# micromousev2.net
KiCad netlist of a schematic drawn in EAGLE
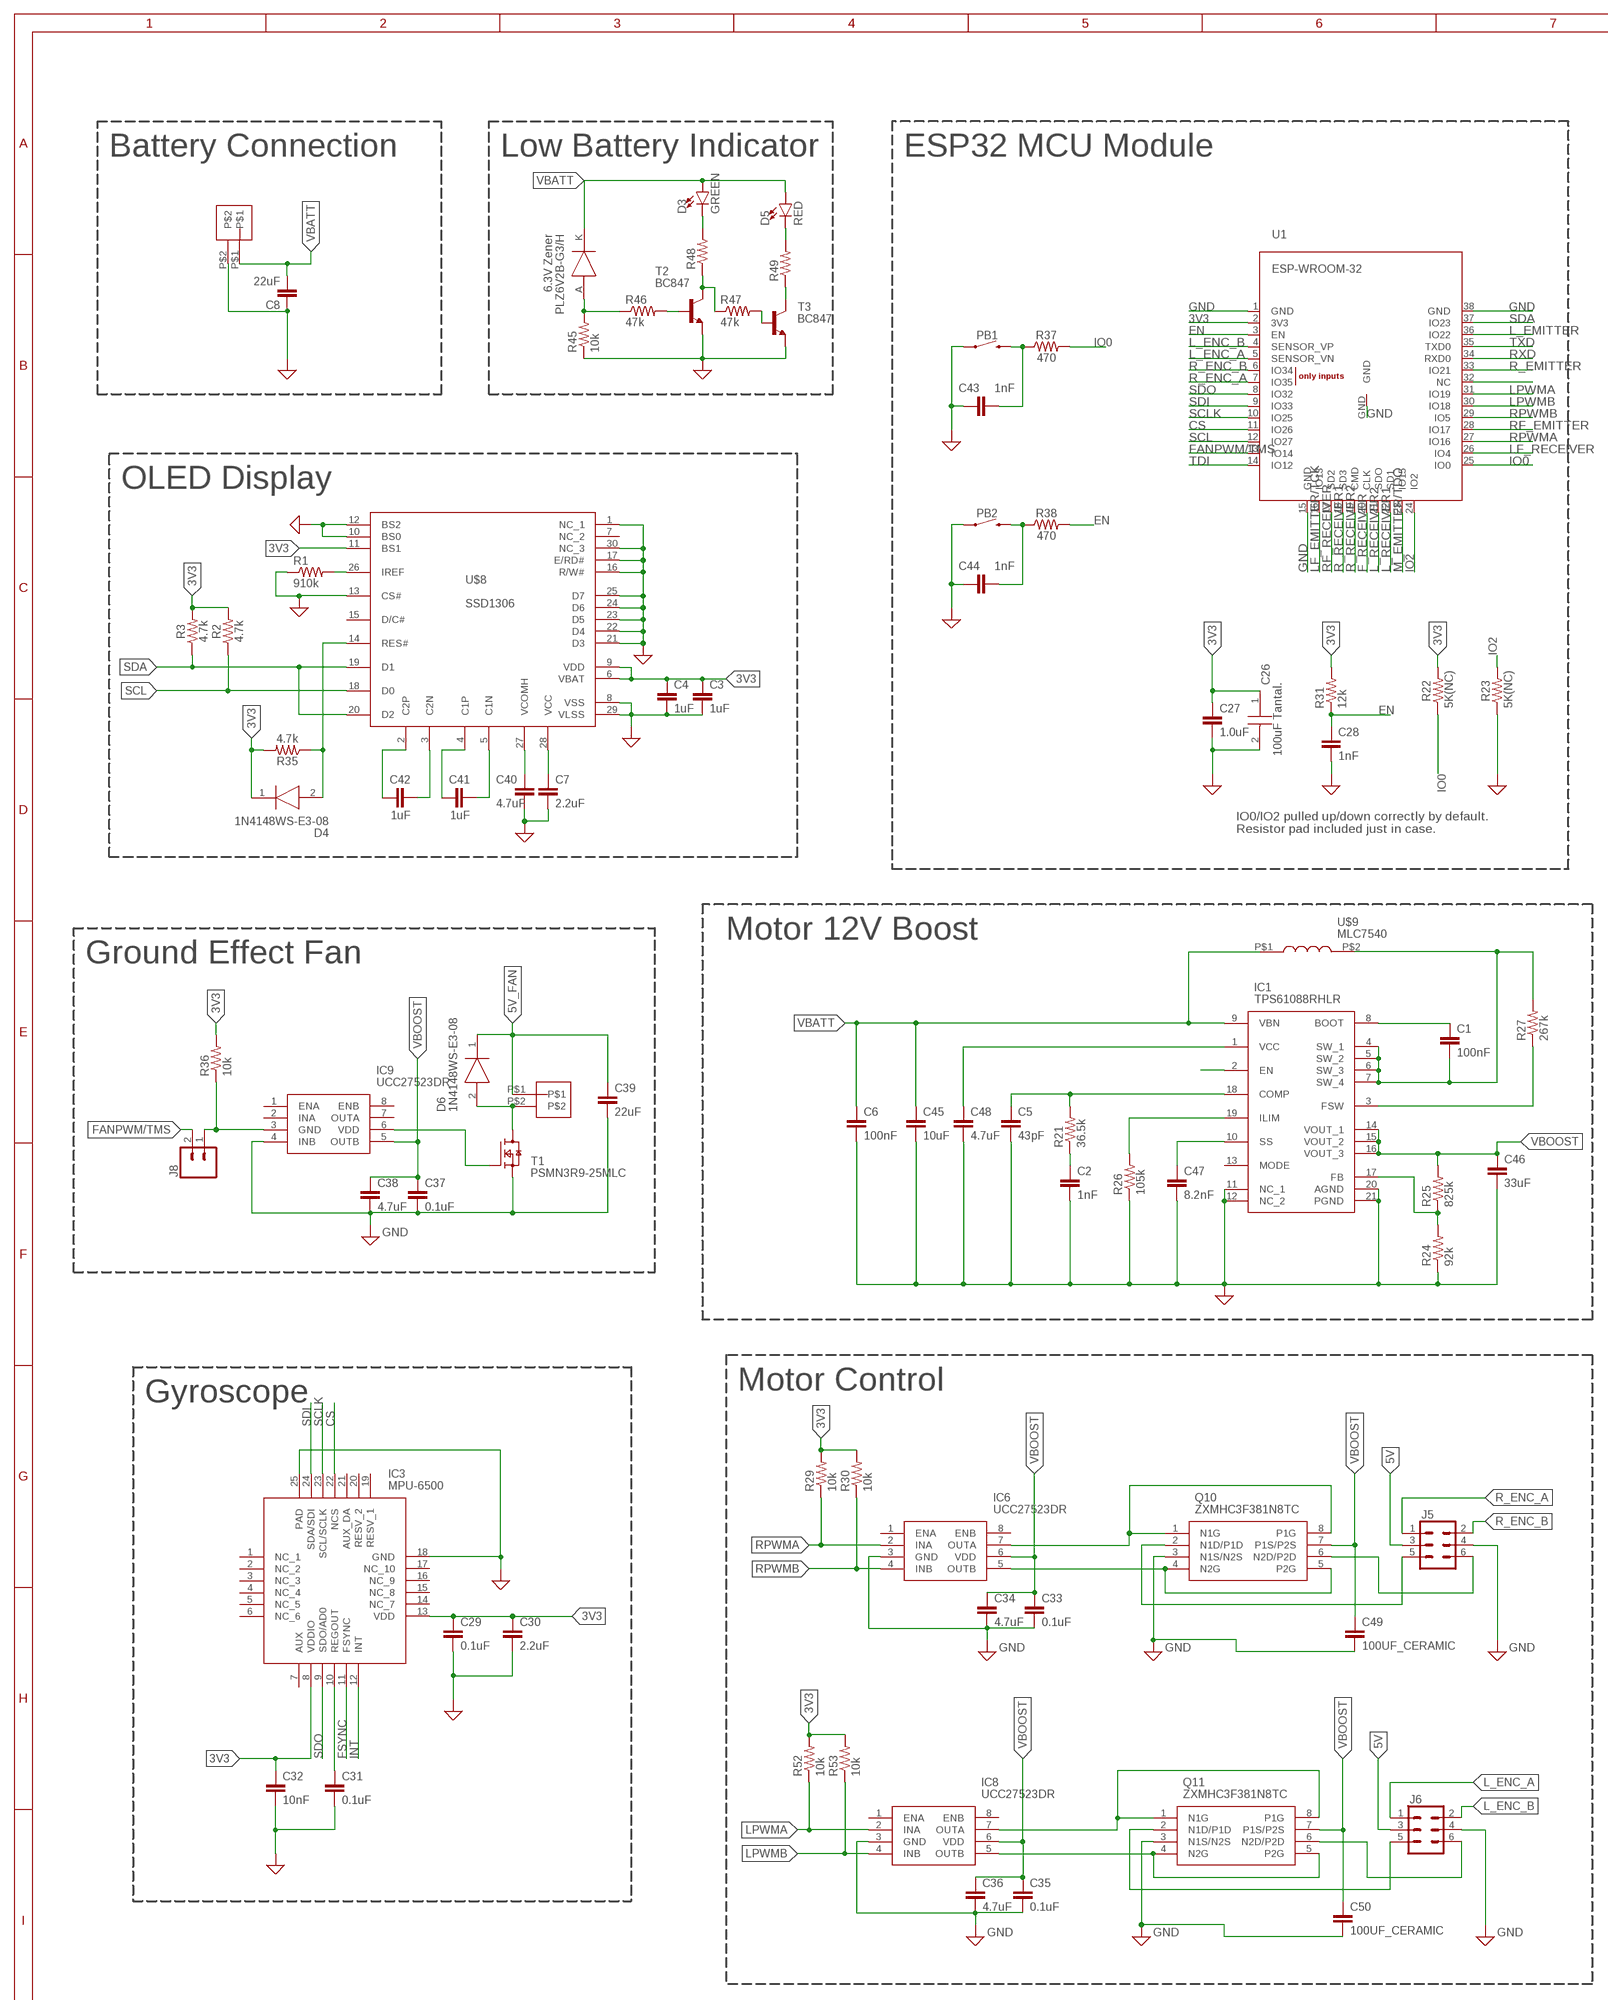
[diagram p0: schematic, sheet 1, part 1 of 2]
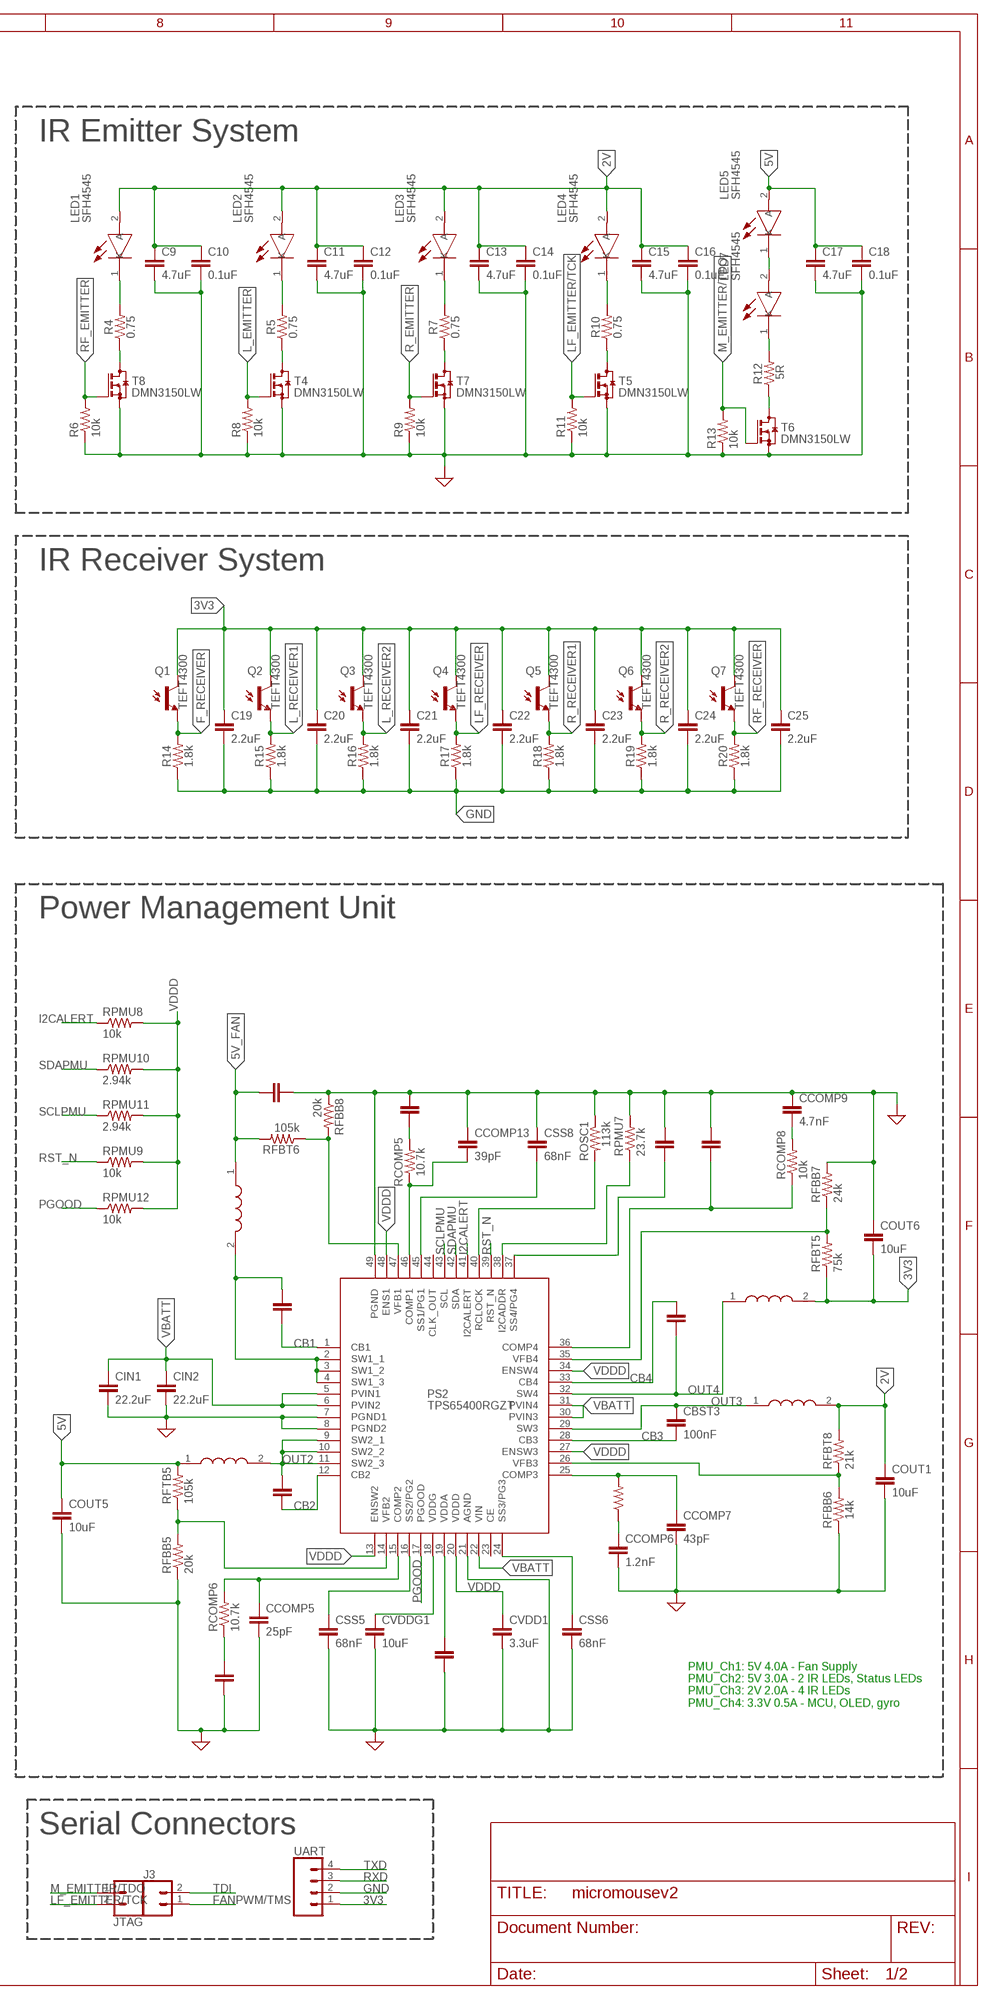
[diagram p1: schematic, sheet 1, part 2 of 2]
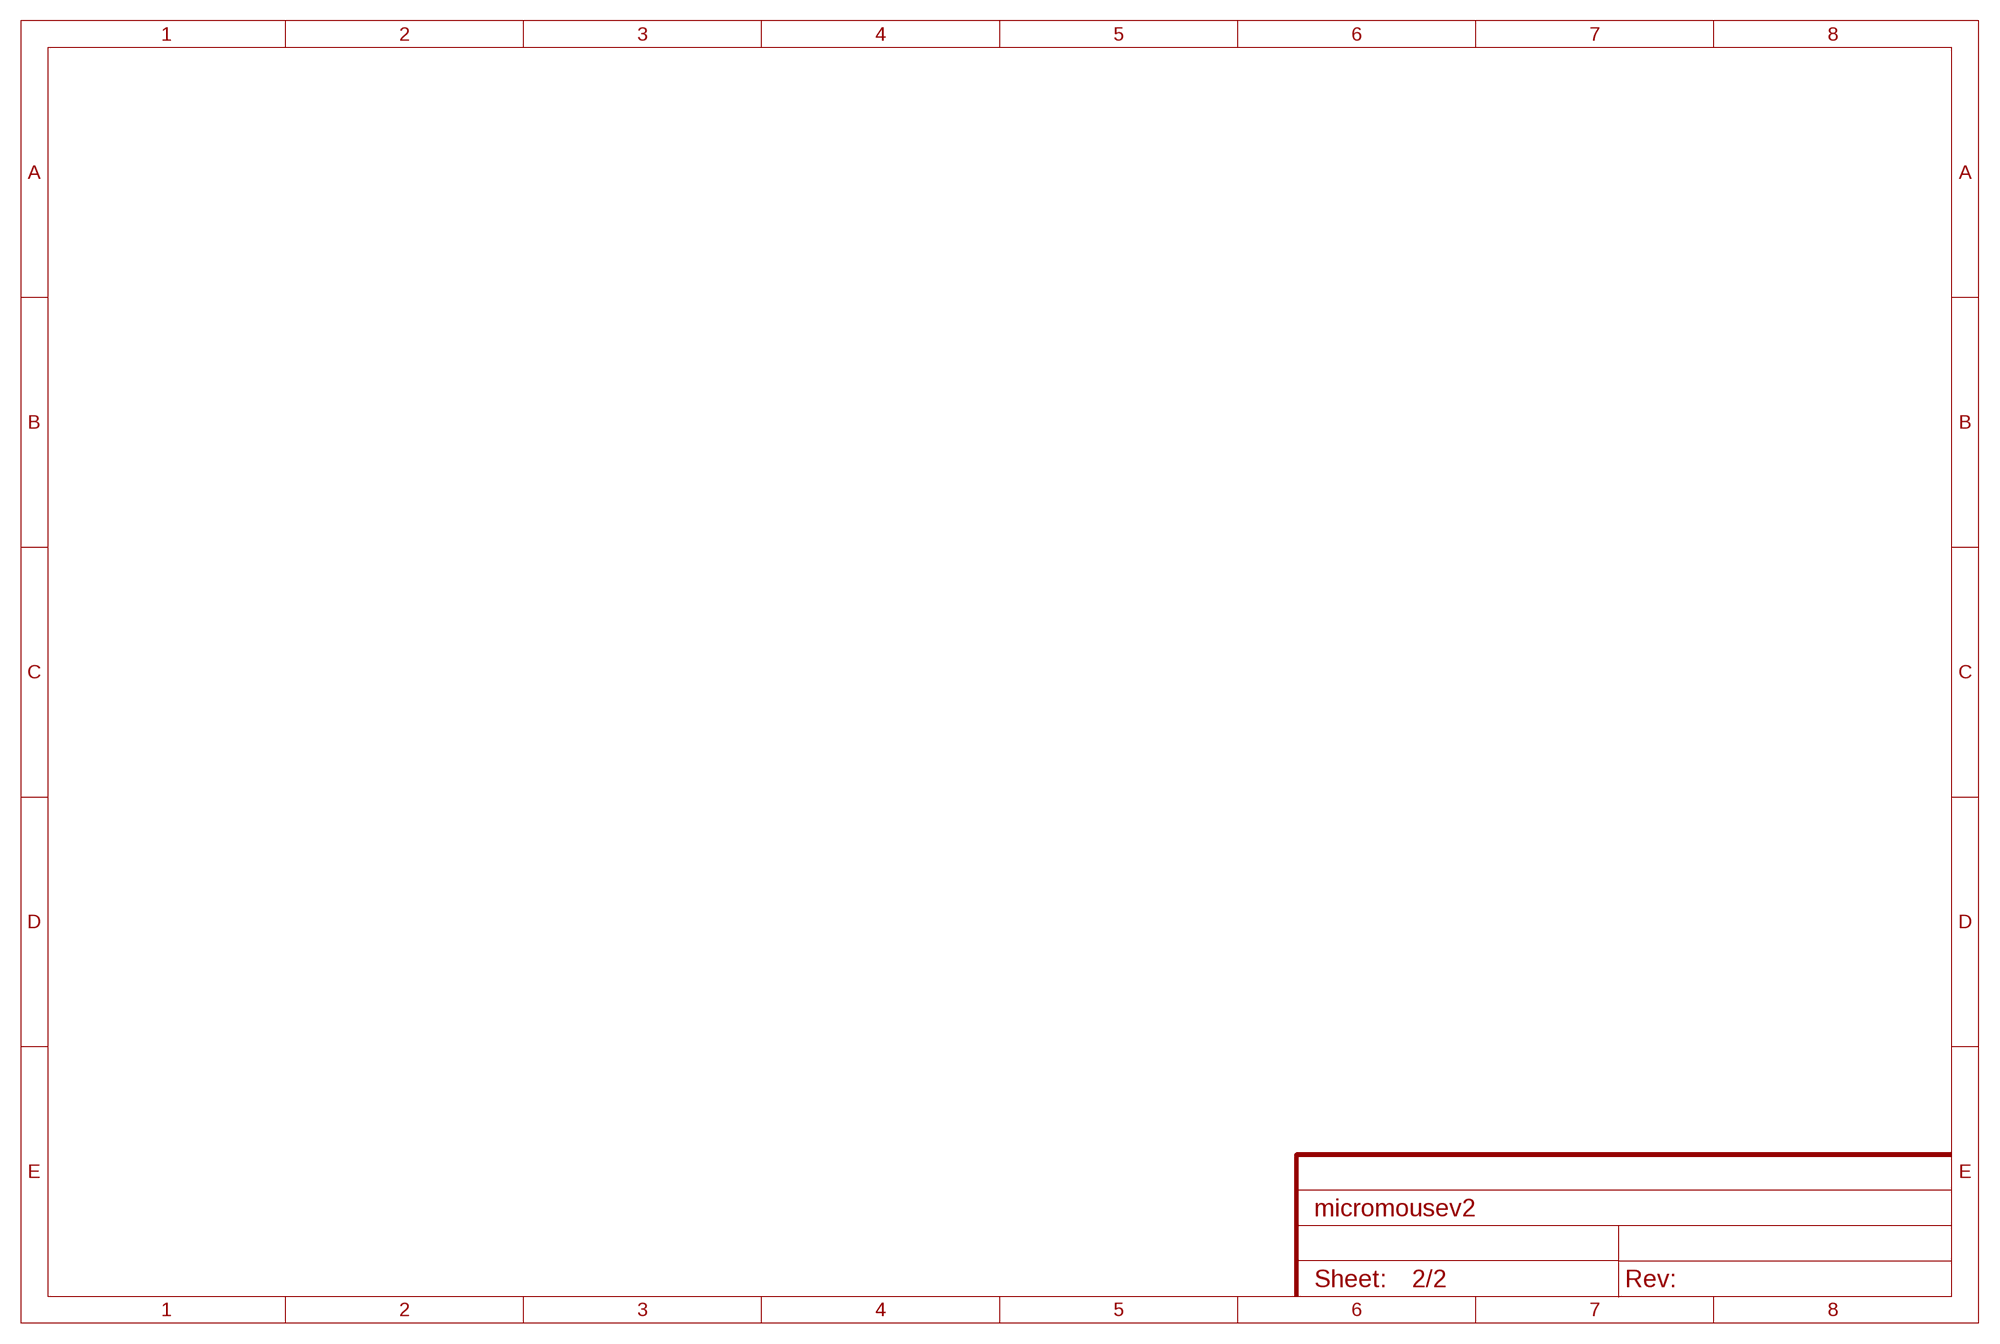
[diagram p2: schematic, sheet 2]

(export (version "E")
  (design (tool "Eeschema 10.0.6"))
  (components
    (comp (ref "C1")
      (value "100nF")
      (footprint "eagle-import:C0402")
      (libsource (lib "eagle-import") (part "C-EUC0402"))
    )
    (comp (ref "C2")
      (value "1nF")
      (footprint "eagle-import:C0805")
      (libsource (lib "eagle-import") (part "C-EUC0805"))
    )
    (comp (ref "C3")
      (value "1uF")
      (footprint "eagle-import:C0402")
      (libsource (lib "eagle-import") (part "resistor_348_C-EUC0402"))
    )
    (comp (ref "C4")
      (value "1uF")
      (footprint "eagle-import:C0402")
      (libsource (lib "eagle-import") (part "resistor_348_C-EUC0402"))
    )
    (comp (ref "C5")
      (value "43pF")
      (footprint "eagle-import:C0402")
      (libsource (lib "eagle-import") (part "C-EUC0402"))
    )
    (comp (ref "C6")
      (value "100nF")
      (footprint "eagle-import:C0805")
      (libsource (lib "eagle-import") (part "C-EUC0805"))
    )
    (comp (ref "C7")
      (value "2.2uF")
      (footprint "eagle-import:C0402")
      (libsource (lib "eagle-import") (part "resistor_348_C-EUC0402"))
    )
    (comp (ref "C8")
      (value "22uF")
      (footprint "eagle-import:0805")
      (libsource (lib "eagle-import") (part "22UF-0805-6.3V-20%"))
    )
    (comp (ref "C9")
      (value "4.7uF")
      (footprint "eagle-import:0603")
      (libsource (lib "eagle-import") (part "4.7UF0603"))
    )
    (comp (ref "C10")
      (value "0.1uF")
      (footprint "eagle-import:C0402")
      (libsource (lib "eagle-import") (part "C-EUC0402"))
    )
    (comp (ref "C11")
      (value "4.7uF")
      (footprint "eagle-import:0603")
      (libsource (lib "eagle-import") (part "4.7UF0603"))
    )
    (comp (ref "C12")
      (value "0.1uF")
      (footprint "eagle-import:C0402")
      (libsource (lib "eagle-import") (part "C-EUC0402"))
    )
    (comp (ref "C13")
      (value "4.7uF")
      (footprint "eagle-import:0603")
      (libsource (lib "eagle-import") (part "4.7UF0603"))
    )
    (comp (ref "C14")
      (value "0.1uF")
      (footprint "eagle-import:C0402")
      (libsource (lib "eagle-import") (part "C-EUC0402"))
    )
    (comp (ref "C15")
      (value "4.7uF")
      (footprint "eagle-import:0603")
      (libsource (lib "eagle-import") (part "4.7UF0603"))
    )
    (comp (ref "C16")
      (value "0.1uF")
      (footprint "eagle-import:C0402")
      (libsource (lib "eagle-import") (part "C-EUC0402"))
    )
    (comp (ref "C17")
      (value "4.7uF")
      (footprint "eagle-import:0603")
      (libsource (lib "eagle-import") (part "4.7UF0603"))
    )
    (comp (ref "C18")
      (value "0.1uF")
      (footprint "eagle-import:C0402")
      (libsource (lib "eagle-import") (part "C-EUC0402"))
    )
    (comp (ref "C19")
      (value "2.2uF")
      (footprint "eagle-import:0603")
      (libsource (lib "eagle-import") (part "2.2UF-0603-10V-20%"))
    )
    (comp (ref "C20")
      (value "2.2uF")
      (footprint "eagle-import:0603")
      (libsource (lib "eagle-import") (part "2.2UF-0603-10V-20%"))
    )
    (comp (ref "C21")
      (value "2.2uF")
      (footprint "eagle-import:0603")
      (libsource (lib "eagle-import") (part "2.2UF-0603-10V-20%"))
    )
    (comp (ref "C22")
      (value "2.2uF")
      (footprint "eagle-import:0603")
      (libsource (lib "eagle-import") (part "2.2UF-0603-10V-20%"))
    )
    (comp (ref "C23")
      (value "2.2uF")
      (footprint "eagle-import:0603")
      (libsource (lib "eagle-import") (part "2.2UF-0603-10V-20%"))
    )
    (comp (ref "C24")
      (value "2.2uF")
      (footprint "eagle-import:0603")
      (libsource (lib "eagle-import") (part "2.2UF-0603-10V-20%"))
    )
    (comp (ref "C25")
      (value "2.2uF")
      (footprint "eagle-import:0603")
      (libsource (lib "eagle-import") (part "2.2UF-0603-10V-20%"))
    )
    (comp (ref "C26")
      (value "100uF Tantal.")
      (footprint "eagle-import:CAPPM3528X210N")
      (fields (field (name "ARROW_PART_NUMBER") "TPSB107K006R0400") (field (name "RS_PART_NUMBER") "1243324"))
      (libsource (lib "eagle-import") (part "TPSB107K006R0400"))
    )
    (comp (ref "C27")
      (value "1.0uF")
      (footprint "eagle-import:0402")
      (libsource (lib "eagle-import") (part "1.0UF-0402-16V-10%"))
    )
    (comp (ref "C28")
      (value "1nF")
      (footprint "eagle-import:0603")
      (libsource (lib "eagle-import") (part "1.0NF/1000PF-0603-50V-10%"))
    )
    (comp (ref "C29")
      (value "0.1uF")
      (footprint "eagle-import:0603")
      (libsource (lib "eagle-import") (part "0.1UF-0603-25V-(+80/-20%)"))
    )
    (comp (ref "C30")
      (value "2.2uF")
      (footprint "eagle-import:0603")
      (libsource (lib "eagle-import") (part "2.2UF-0603-10V-20%"))
    )
    (comp (ref "C31")
      (value "0.1uF")
      (footprint "eagle-import:0603")
      (libsource (lib "eagle-import") (part "0.1UF-0603-25V-(+80/-20%)"))
    )
    (comp (ref "C32")
      (value "10nF")
      (footprint "eagle-import:0603")
      (libsource (lib "eagle-import") (part "10NF-0603-50V-10%"))
    )
    (comp (ref "C33")
      (value "0.1uF")
      (footprint "eagle-import:0603")
      (libsource (lib "eagle-import") (part "0.1UF-0603-25V-(+80/-20%)"))
    )
    (comp (ref "C34")
      (value "4.7uF")
      (footprint "eagle-import:0603")
      (libsource (lib "eagle-import") (part "4.7UF0603"))
    )
    (comp (ref "C35")
      (value "0.1uF")
      (footprint "eagle-import:0603")
      (libsource (lib "eagle-import") (part "0.1UF-0603-25V-(+80/-20%)"))
    )
    (comp (ref "C36")
      (value "4.7uF")
      (footprint "eagle-import:0603")
      (libsource (lib "eagle-import") (part "4.7UF0603"))
    )
    (comp (ref "C37")
      (value "0.1uF")
      (footprint "eagle-import:0603")
      (libsource (lib "eagle-import") (part "0.1UF-0603-25V-(+80/-20%)"))
    )
    (comp (ref "C38")
      (value "4.7uF")
      (footprint "eagle-import:0603")
      (libsource (lib "eagle-import") (part "4.7UF0603"))
    )
    (comp (ref "C39")
      (value "22uF")
      (footprint "eagle-import:0805")
      (libsource (lib "eagle-import") (part "22UF-0805-6.3V-20%"))
    )
    (comp (ref "C40")
      (value "4.7uF")
      (footprint "eagle-import:C0402")
      (libsource (lib "eagle-import") (part "resistor_348_C-EUC0402"))
    )
    (comp (ref "C41")
      (value "1uF")
      (footprint "eagle-import:C0402")
      (libsource (lib "eagle-import") (part "resistor_348_C-EUC0402"))
    )
    (comp (ref "C42")
      (value "1uF")
      (footprint "eagle-import:C0402")
      (libsource (lib "eagle-import") (part "resistor_348_C-EUC0402"))
    )
    (comp (ref "C43")
      (value "1nF")
      (footprint "eagle-import:0603")
      (libsource (lib "eagle-import") (part "1.0NF/1000PF-0603-50V-10%"))
    )
    (comp (ref "C44")
      (value "1nF")
      (footprint "eagle-import:0603")
      (libsource (lib "eagle-import") (part "1.0NF/1000PF-0603-50V-10%"))
    )
    (comp (ref "C45")
      (value "10uF")
      (footprint "eagle-import:C0402")
      (libsource (lib "eagle-import") (part "C-EUC0402"))
    )
    (comp (ref "C46")
      (value "33uF")
      (footprint "eagle-import:C1206")
      (libsource (lib "eagle-import") (part "C-EUC1206"))
    )
    (comp (ref "C47")
      (value "8.2nF")
      (footprint "eagle-import:C0805")
      (libsource (lib "eagle-import") (part "C-EUC0805"))
    )
    (comp (ref "C48")
      (value "4.7uF")
      (footprint "eagle-import:C0402")
      (libsource (lib "eagle-import") (part "C-EUC0402"))
    )
    (comp (ref "C49")
      (value "100UF_CERAMIC")
      (footprint "eagle-import:C1210")
      (libsource (lib "eagle-import") (part "100UF_CERAMIC"))
    )
    (comp (ref "C50")
      (value "100UF_CERAMIC")
      (footprint "eagle-import:C1210")
      (libsource (lib "eagle-import") (part "100UF_CERAMIC"))
    )
    (comp (ref "CBST1")
      (value "100nF")
      (footprint "eagle-import:C0402")
      (libsource (lib "eagle-import") (part "resistor_348_C-EUC0402"))
    )
    (comp (ref "CBST2")
      (value "100nF")
      (footprint "eagle-import:C0402")
      (libsource (lib "eagle-import") (part "resistor_348_C-EUC0402"))
    )
    (comp (ref "CBST3")
      (value "100nF")
      (footprint "eagle-import:C0402")
      (libsource (lib "eagle-import") (part "resistor_348_C-EUC0402"))
    )
    (comp (ref "CBST4")
      (value "100nF")
      (footprint "eagle-import:C0402")
      (libsource (lib "eagle-import") (part "resistor_348_C-EUC0402"))
    )
    (comp (ref "CCOMP5")
      (value "25pF")
      (footprint "eagle-import:C0603")
      (libsource (lib "eagle-import") (part "C-EUC0603"))
    )
    (comp (ref "CCOMP6")
      (value "1.2nF")
      (footprint "eagle-import:C0603")
      (libsource (lib "eagle-import") (part "C-EUC0603"))
    )
    (comp (ref "CCOMP7")
      (value "43pF")
      (footprint "eagle-import:C0603")
      (libsource (lib "eagle-import") (part "resistor_348_C-EUC0603"))
    )
    (comp (ref "CCOMP8")
      (value "1.8nF")
      (footprint "eagle-import:C0603")
      (libsource (lib "eagle-import") (part "resistor_348_C-EUC0603"))
    )
    (comp (ref "CCOMP9")
      (value "4.7nF")
      (footprint "eagle-import:C0603")
      (libsource (lib "eagle-import") (part "C-EUC0603"))
    )
    (comp (ref "CCOMP10")
      (value "82pF")
      (footprint "eagle-import:C0603")
      (libsource (lib "eagle-import") (part "C-EUC0603"))
    )
    (comp (ref "CCOMP11")
      (value "1.2nF")
      (footprint "eagle-import:C0603")
      (libsource (lib "eagle-import") (part "resistor_348_C-EUC0603"))
    )
    (comp (ref "CCOMP13")
      (value "39pF")
      (footprint "eagle-import:C0603")
      (libsource (lib "eagle-import") (part "resistor_348_C-EUC0603"))
    )
    (comp (ref "CIN1")
      (value "22.2uF")
      (footprint "eagle-import:0805")
      (libsource (lib "eagle-import") (part "10UF-0805-10V-10%"))
    )
    (comp (ref "CIN2")
      (value "22.2uF")
      (footprint "eagle-import:0805")
      (libsource (lib "eagle-import") (part "10UF-0805-10V-10%"))
    )
    (comp (ref "CIN3")
      (value "22.2uF")
      (footprint "eagle-import:0805")
      (libsource (lib "eagle-import") (part "10UF-0805-10V-10%"))
    )
    (comp (ref "COUT1")
      (value "10uF")
      (footprint "eagle-import:C0402")
      (libsource (lib "eagle-import") (part "resistor_348_C-EUC0402"))
    )
    (comp (ref "COUT5")
      (value "10uF")
      (footprint "eagle-import:C0402")
      (libsource (lib "eagle-import") (part "resistor_348_C-EUC0402"))
    )
    (comp (ref "COUT6")
      (value "10uF")
      (footprint "eagle-import:C0402")
      (libsource (lib "eagle-import") (part "resistor_348_C-EUC0402"))
    )
    (comp (ref "CSS5")
      (value "68nF")
      (footprint "eagle-import:C0402")
      (libsource (lib "eagle-import") (part "resistor_348_C-EUC0402"))
    )
    (comp (ref "CSS6")
      (value "68nF")
      (footprint "eagle-import:C0402")
      (libsource (lib "eagle-import") (part "resistor_348_C-EUC0402"))
    )
    (comp (ref "CSS7")
      (value "68nF")
      (footprint "eagle-import:C0402")
      (libsource (lib "eagle-import") (part "resistor_348_C-EUC0402"))
    )
    (comp (ref "CSS8")
      (value "68nF")
      (footprint "eagle-import:C0402")
      (libsource (lib "eagle-import") (part "resistor_348_C-EUC0402"))
    )
    (comp (ref "CVDD1")
      (value "3.3uF")
      (footprint "eagle-import:C0402")
      (libsource (lib "eagle-import") (part "resistor_348_C-EUC0402"))
    )
    (comp (ref "CVDDA1")
      (value "4.7uF")
      (footprint "eagle-import:0603")
      (libsource (lib "eagle-import") (part "4.7UF0603"))
    )
    (comp (ref "CVDDG1")
      (value "10uF")
      (footprint "eagle-import:C0603")
      (libsource (lib "eagle-import") (part "resistor_348_C-EUC0603"))
    )
    (comp (ref "D3")
      (value "GREEN")
      (footprint "eagle-import:LED-0603")
      (libsource (lib "eagle-import") (part "LED-GREEN0603"))
    )
    (comp (ref "D4")
      (value "1N4148WS-E3-08")
      (footprint "eagle-import:SOD2713X115N")
      (fields (field (name "RS_PART_NUMBER") "7003677P"))
      (libsource (lib "eagle-import") (part "1N4148WS-E3-08"))
    )
    (comp (ref "D5")
      (value "RED")
      (footprint "eagle-import:LED-0603")
      (libsource (lib "eagle-import") (part "LED-RED0603"))
    )
    (comp (ref "D6")
      (value "1N4148WS-E3-08")
      (footprint "eagle-import:SOD2713X115N")
      (fields (field (name "RS_PART_NUMBER") "7003677P"))
      (libsource (lib "eagle-import") (part "1N4148WS-E3-08"))
    )
    (comp (ref "IC1")
      (value "TPS61088RHLR")
      (footprint "eagle-import:RHL(R-PVQFN-N20)_1")
      (libsource (lib "eagle-import") (part "TPS61088RHLR"))
    )
    (comp (ref "IC3")
      (value "MPU-6500")
      (footprint "eagle-import:QFN40P300X300X95-25N")
      (libsource (lib "eagle-import") (part "MPU-6500"))
    )
    (comp (ref "IC6")
      (value "UCC27523DR")
      (footprint "eagle-import:SOIC127P600X175-8N")
      (libsource (lib "eagle-import") (part "UCC27523DR"))
    )
    (comp (ref "IC8")
      (value "UCC27523DR")
      (footprint "eagle-import:SOIC127P600X175-8N")
      (libsource (lib "eagle-import") (part "UCC27523DR"))
    )
    (comp (ref "IC9")
      (value "UCC27523DR")
      (footprint "eagle-import:SOIC127P600X175-8N")
      (libsource (lib "eagle-import") (part "UCC27523DR"))
    )
    (comp (ref "J2")
      (value "2_PIN_JST-XH")
      (footprint "eagle-import:2_PIN_JST-XH")
      (libsource (lib "eagle-import") (part "2_PIN_JST-XH"))
    )
    (comp (ref "J3")
      (value "CONN_02")
      (footprint "eagle-import:1X02")
      (libsource (lib "eagle-import") (part "CONN_02"))
    )
    (comp (ref "J5")
      (value "CONN_03X22X3_SILK_MALE_PTH")
      (footprint "eagle-import:2X3")
      (libsource (lib "eagle-import") (part "CONN_03X22X3_SILK_MALE_PTH"))
    )
    (comp (ref "J6")
      (value "CONN_03X22X3_SILK_MALE_PTH")
      (footprint "eagle-import:2X3")
      (libsource (lib "eagle-import") (part "CONN_03X22X3_SILK_MALE_PTH"))
    )
    (comp (ref "J7")
      (value "2_PIN_JST-XH")
      (footprint "eagle-import:2_PIN_JST-XH")
      (libsource (lib "eagle-import") (part "2_PIN_JST-XH"))
    )
    (comp (ref "J8")
      (value "CONN_02")
      (footprint "eagle-import:1X02")
      (libsource (lib "eagle-import") (part "CONN_02"))
    )
    (comp (ref "JTAG")
      (value "CONN_02")
      (footprint "eagle-import:1X02")
      (libsource (lib "eagle-import") (part "CONN_02"))
    )
    (comp (ref "L5")
      (value "XAL4030-332MEB")
      (footprint "eagle-import:XAL4030-332MEB")
      (libsource (lib "eagle-import") (part "XAL4030-332MEB"))
    )
    (comp (ref "L6")
      (value "SDR0302-100ML")
      (footprint "eagle-import:SDR0302-471KL")
      (fields (field (name "ARROW_PART_NUMBER") "SDR0302-1R2ML"))
      (libsource (lib "eagle-import") (part "SDR0302-1R2ML"))
    )
    (comp (ref "L7")
      (value "XAL4030-472MEB")
      (footprint "eagle-import:XAL4030-332MEB")
      (fields (field (name "ARROW_PART_NUMBER") "XAL4030-332MEB"))
      (libsource (lib "eagle-import") (part "XAL4030-332MEB"))
    )
    (comp (ref "L8")
      (value "XFL4020-472MEB")
      (footprint "eagle-import:XFL4020-222ME")
      (fields (field (name "ARROW_PART_NUMBER") "XFL4020-332MEB"))
      (libsource (lib "eagle-import") (part "XFL4020-332MEB"))
    )
    (comp (ref "LED1")
      (value "SFH4545")
      (footprint "eagle-import:SFH_4556P")
      (fields (field (name "ARROW_PART_NUMBER") "SFH4550"))
      (libsource (lib "eagle-import") (part "SFH4550"))
    )
    (comp (ref "LED2")
      (value "SFH4545")
      (footprint "eagle-import:SFH_4556P")
      (fields (field (name "ARROW_PART_NUMBER") "SFH4550"))
      (libsource (lib "eagle-import") (part "SFH4550"))
    )
    (comp (ref "LED3")
      (value "SFH4545")
      (footprint "eagle-import:SFH_4556P")
      (fields (field (name "ARROW_PART_NUMBER") "SFH4550"))
      (libsource (lib "eagle-import") (part "SFH4550"))
    )
    (comp (ref "LED4")
      (value "SFH4545")
      (footprint "eagle-import:SFH_4556P")
      (fields (field (name "ARROW_PART_NUMBER") "SFH4550"))
      (libsource (lib "eagle-import") (part "SFH4550"))
    )
    (comp (ref "LED5")
      (value "SFH4545")
      (footprint "eagle-import:SFH_4556P")
      (fields (field (name "ARROW_PART_NUMBER") "SFH4550"))
      (libsource (lib "eagle-import") (part "SFH4550"))
    )
    (comp (ref "LED7")
      (value "SFH4545")
      (footprint "eagle-import:SFH_4556P")
      (fields (field (name "ARROW_PART_NUMBER") "SFH4550"))
      (libsource (lib "eagle-import") (part "SFH4550"))
    )
    (comp (ref "PB1")
      (value "SPST_3X6X2.5MMPB")
      (footprint "eagle-import:3X6X2.5MMSPB")
      (libsource (lib "eagle-import") (part "SPST_3X6X2.5MMPB"))
    )
    (comp (ref "PB2")
      (value "SPST_3X6X2.5MMPB")
      (footprint "eagle-import:3X6X2.5MMSPB")
      (libsource (lib "eagle-import") (part "SPST_3X6X2.5MMPB"))
    )
    (comp (ref "PLZ6V2B-G3/H")
      (value "6.3V Zener")
      (footprint "eagle-import:DO-219AC")
      (libsource (lib "eagle-import") (part "PLZ6V8C-HG3/H"))
    )
    (comp (ref "PS2")
      (value "TPS65400RGZT")
      (footprint "eagle-import:QFN50P700X700X100-49N")
      (fields (field (name "RS_PART_NUMBER") "1629904"))
      (libsource (lib "eagle-import") (part "TPS65400RGZT"))
    )
    (comp (ref "Q1")
      (value "TEFT4300")
      (footprint "eagle-import:TEFT4300")
      (fields (field (name "RS_PART_NUMBER") "7082731P"))
      (libsource (lib "eagle-import") (part "TEFT4300"))
    )
    (comp (ref "Q2")
      (value "TEFT4300")
      (footprint "eagle-import:TEFT4300")
      (fields (field (name "RS_PART_NUMBER") "7082731P"))
      (libsource (lib "eagle-import") (part "TEFT4300"))
    )
    (comp (ref "Q3")
      (value "TEFT4300")
      (footprint "eagle-import:TEFT4300")
      (fields (field (name "RS_PART_NUMBER") "7082731P"))
      (libsource (lib "eagle-import") (part "TEFT4300"))
    )
    (comp (ref "Q4")
      (value "TEFT4300")
      (footprint "eagle-import:TEFT4300")
      (fields (field (name "RS_PART_NUMBER") "7082731P"))
      (libsource (lib "eagle-import") (part "TEFT4300"))
    )
    (comp (ref "Q5")
      (value "TEFT4300")
      (footprint "eagle-import:TEFT4300")
      (fields (field (name "RS_PART_NUMBER") "7082731P"))
      (libsource (lib "eagle-import") (part "TEFT4300"))
    )
    (comp (ref "Q6")
      (value "TEFT4300")
      (footprint "eagle-import:TEFT4300")
      (fields (field (name "RS_PART_NUMBER") "7082731P"))
      (libsource (lib "eagle-import") (part "TEFT4300"))
    )
    (comp (ref "Q7")
      (value "TEFT4300")
      (footprint "eagle-import:TEFT4300")
      (fields (field (name "RS_PART_NUMBER") "7082731P"))
      (libsource (lib "eagle-import") (part "TEFT4300"))
    )
    (comp (ref "Q10")
      (value "ZXMHC3F381N8TC")
      (footprint "eagle-import:SOIC127P600X175-8N")
      (fields (field (name "RS_PART_NUMBER") "7515344P"))
      (libsource (lib "eagle-import") (part "ZXMHC3F381N8TC"))
    )
    (comp (ref "Q11")
      (value "ZXMHC3F381N8TC")
      (footprint "eagle-import:SOIC127P600X175-8N")
      (fields (field (name "RS_PART_NUMBER") "7515344P"))
      (libsource (lib "eagle-import") (part "ZXMHC3F381N8TC"))
    )
    (comp (ref "R1")
      (value "910k")
      (footprint "eagle-import:R0402")
      (libsource (lib "eagle-import") (part "R-US_R0402"))
    )
    (comp (ref "R2")
      (value "4.7k")
      (footprint "eagle-import:0603")
      (libsource (lib "eagle-import") (part "4.7KOHM-0603-1/10W-1%"))
    )
    (comp (ref "R3")
      (value "4.7k")
      (footprint "eagle-import:0603")
      (libsource (lib "eagle-import") (part "4.7KOHM-0603-1/10W-1%"))
    )
    (comp (ref "R4")
      (value "0.75")
      (footprint "eagle-import:0805")
      (libsource (lib "eagle-import") (part "0.75OHM-0805-1/4W-1%"))
    )
    (comp (ref "R5")
      (value "0.75")
      (footprint "eagle-import:0805")
      (libsource (lib "eagle-import") (part "0.75OHM-0805-1/4W-1%"))
    )
    (comp (ref "R6")
      (value "10k")
      (footprint "eagle-import:R0201")
      (libsource (lib "eagle-import") (part "R-US_R0201"))
    )
    (comp (ref "R7")
      (value "0.75")
      (footprint "eagle-import:0805")
      (libsource (lib "eagle-import") (part "0.75OHM-0805-1/4W-1%"))
    )
    (comp (ref "R8")
      (value "10k")
      (footprint "eagle-import:R0201")
      (libsource (lib "eagle-import") (part "R-US_R0201"))
    )
    (comp (ref "R9")
      (value "10k")
      (footprint "eagle-import:R0201")
      (libsource (lib "eagle-import") (part "R-US_R0201"))
    )
    (comp (ref "R10")
      (value "0.75")
      (footprint "eagle-import:0805")
      (libsource (lib "eagle-import") (part "0.75OHM-0805-1/4W-1%"))
    )
    (comp (ref "R11")
      (value "10k")
      (footprint "eagle-import:R0201")
      (libsource (lib "eagle-import") (part "R-US_R0201"))
    )
    (comp (ref "R12")
      (value "5R")
      (footprint "eagle-import:0805")
      (libsource (lib "eagle-import") (part "RESISTOR0805"))
    )
    (comp (ref "R13")
      (value "10k")
      (footprint "eagle-import:R0201")
      (libsource (lib "eagle-import") (part "R-US_R0201"))
    )
    (comp (ref "R14")
      (value "1.8k")
      (footprint "eagle-import:0603")
      (libsource (lib "eagle-import") (part "1.8KOHM-0603-1/10W-1%"))
    )
    (comp (ref "R15")
      (value "1.8k")
      (footprint "eagle-import:0603")
      (libsource (lib "eagle-import") (part "1.8KOHM-0603-1/10W-1%"))
    )
    (comp (ref "R16")
      (value "1.8k")
      (footprint "eagle-import:0603")
      (libsource (lib "eagle-import") (part "1.8KOHM-0603-1/10W-1%"))
    )
    (comp (ref "R17")
      (value "1.8k")
      (footprint "eagle-import:0603")
      (libsource (lib "eagle-import") (part "1.8KOHM-0603-1/10W-1%"))
    )
    (comp (ref "R18")
      (value "1.8k")
      (footprint "eagle-import:0603")
      (libsource (lib "eagle-import") (part "1.8KOHM-0603-1/10W-1%"))
    )
    (comp (ref "R19")
      (value "1.8k")
      (footprint "eagle-import:0603")
      (libsource (lib "eagle-import") (part "1.8KOHM-0603-1/10W-1%"))
    )
    (comp (ref "R20")
      (value "1.8k")
      (footprint "eagle-import:0603")
      (libsource (lib "eagle-import") (part "1.8KOHM-0603-1/10W-1%"))
    )
    (comp (ref "R21")
      (value "36.5k")
      (footprint "eagle-import:R0201")
      (libsource (lib "eagle-import") (part "R-US_R0201"))
    )
    (comp (ref "R22")
      (value "5K(NC)")
      (footprint "eagle-import:0402")
      (libsource (lib "eagle-import") (part "RESISTOR0402"))
    )
    (comp (ref "R23")
      (value "5K(NC)")
      (footprint "eagle-import:0402")
      (libsource (lib "eagle-import") (part "RESISTOR0402"))
    )
    (comp (ref "R24")
      (value "92k")
      (footprint "eagle-import:R0805")
      (libsource (lib "eagle-import") (part "R-US_R0805"))
    )
    (comp (ref "R25")
      (value "825k")
      (footprint "eagle-import:R0402")
      (libsource (lib "eagle-import") (part "R-US_R0402"))
    )
    (comp (ref "R26")
      (value "105k")
      (footprint "eagle-import:R0201")
      (libsource (lib "eagle-import") (part "R-US_R0201"))
    )
    (comp (ref "R27")
      (value "267k")
      (footprint "eagle-import:R0402")
      (libsource (lib "eagle-import") (part "R-US_R0402"))
    )
    (comp (ref "R29")
      (value "10k")
      (footprint "eagle-import:R0201")
      (libsource (lib "eagle-import") (part "R-US_R0201"))
    )
    (comp (ref "R30")
      (value "10k")
      (footprint "eagle-import:R0201")
      (libsource (lib "eagle-import") (part "R-US_R0201"))
    )
    (comp (ref "R31")
      (value "12k")
      (footprint "eagle-import:R0201")
      (libsource (lib "eagle-import") (part "R-US_R0201"))
    )
    (comp (ref "R35")
      (value "4.7k")
      (footprint "eagle-import:0603")
      (libsource (lib "eagle-import") (part "4.7KOHM-0603-1/10W-1%"))
    )
    (comp (ref "R36")
      (value "10k")
      (footprint "eagle-import:R0201")
      (libsource (lib "eagle-import") (part "R-US_R0201"))
    )
    (comp (ref "R37")
      (value "470")
      (footprint "eagle-import:0603")
      (libsource (lib "eagle-import") (part "470OHM-0603-1/10W-1%"))
    )
    (comp (ref "R38")
      (value "470")
      (footprint "eagle-import:0603")
      (libsource (lib "eagle-import") (part "470OHM-0603-1/10W-1%"))
    )
    (comp (ref "R45")
      (value "10k")
      (footprint "eagle-import:R0402")
      (libsource (lib "eagle-import") (part "R-US_R0402"))
    )
    (comp (ref "R46")
      (value "47k")
      (footprint "eagle-import:R0402")
      (libsource (lib "eagle-import") (part "R-US_R0402"))
    )
    (comp (ref "R47")
      (value "47k")
      (footprint "eagle-import:R0402")
      (libsource (lib "eagle-import") (part "R-US_R0402"))
    )
    (comp (ref "R48")
      (value "R-US_R0603")
      (footprint "eagle-import:R0603")
      (libsource (lib "eagle-import") (part "R-US_R0603"))
    )
    (comp (ref "R49")
      (value "R-US_R0603")
      (footprint "eagle-import:R0603")
      (libsource (lib "eagle-import") (part "R-US_R0603"))
    )
    (comp (ref "R52")
      (value "10k")
      (footprint "eagle-import:R0201")
      (libsource (lib "eagle-import") (part "R-US_R0201"))
    )
    (comp (ref "R53")
      (value "10k")
      (footprint "eagle-import:R0201")
      (libsource (lib "eagle-import") (part "R-US_R0201"))
    )
    (comp (ref "RCOMP5")
      (value "10.7k")
      (footprint "eagle-import:0402")
      (libsource (lib "eagle-import") (part "RESISTOR0402"))
    )
    (comp (ref "RCOMP6")
      (value "10.7k")
      (footprint "eagle-import:R0402")
      (libsource (lib "eagle-import") (part "R-US_R0402"))
    )
    (comp (ref "RCOMP7")
      (value "9.31k")
      (footprint "eagle-import:R0402")
      (libsource (lib "eagle-import") (part "R-US_R0402"))
    )
    (comp (ref "RCOMP8")
      (value "10k")
      (footprint "eagle-import:R0201")
      (libsource (lib "eagle-import") (part "resistor_348_R-US_R0201"))
    )
    (comp (ref "RFBB5")
      (value "20k")
      (footprint "eagle-import:R0805")
      (libsource (lib "eagle-import") (part "resistor_348_R-US_R0805"))
    )
    (comp (ref "RFBB6")
      (value "14k")
      (footprint "eagle-import:0402")
      (libsource (lib "eagle-import") (part "RESISTOR0402"))
    )
    (comp (ref "RFBB7")
      (value "24k")
      (footprint "eagle-import:R0805")
      (libsource (lib "eagle-import") (part "resistor_348_R-US_R0805"))
    )
    (comp (ref "RFBB8")
      (value "20k")
      (footprint "eagle-import:R0805")
      (libsource (lib "eagle-import") (part "R-US_R0805"))
    )
    (comp (ref "RFBT5")
      (value "75k")
      (footprint "eagle-import:R0402")
      (libsource (lib "eagle-import") (part "resistor_348_R-US_R0402"))
    )
    (comp (ref "RFBT6")
      (value "105k")
      (footprint "eagle-import:R0201")
      (libsource (lib "eagle-import") (part "R-US_R0201"))
    )
    (comp (ref "RFBT8")
      (value "21k")
      (footprint "eagle-import:R0402")
      (libsource (lib "eagle-import") (part "R-US_R0402"))
    )
    (comp (ref "RFTB5")
      (value "105k")
      (footprint "eagle-import:R0201")
      (libsource (lib "eagle-import") (part "R-US_R0201"))
    )
    (comp (ref "ROSC1")
      (value "113k")
      (footprint "eagle-import:R0402")
      (libsource (lib "eagle-import") (part "resistor_348_R-US_R0402"))
    )
    (comp (ref "RPMU7")
      (value "23.7k")
      (footprint "eagle-import:R0201")
      (libsource (lib "eagle-import") (part "resistor_348_R-US_R0201"))
    )
    (comp (ref "RPMU8")
      (value "10k")
      (footprint "eagle-import:R0201")
      (libsource (lib "eagle-import") (part "resistor_348_R-US_R0201"))
    )
    (comp (ref "RPMU9")
      (value "10k")
      (footprint "eagle-import:R0201")
      (libsource (lib "eagle-import") (part "resistor_348_R-US_R0201"))
    )
    (comp (ref "RPMU10")
      (value "2.94k")
      (footprint "eagle-import:R0402")
      (libsource (lib "eagle-import") (part "resistor_348_R-US_R0402"))
    )
    (comp (ref "RPMU11")
      (value "2.94k")
      (footprint "eagle-import:R0402")
      (libsource (lib "eagle-import") (part "resistor_348_R-US_R0402"))
    )
    (comp (ref "RPMU12")
      (value "10k")
      (footprint "eagle-import:R0201")
      (libsource (lib "eagle-import") (part "resistor_348_R-US_R0201"))
    )
    (comp (ref "T1")
      (value "PSMN3R9-25MLC")
      (footprint "eagle-import:SOT1210")
      (fields (field (name "VOLTAGE") "25V"))
      (libsource (lib "eagle-import") (part "PSMNMLC3R9-25"))
    )
    (comp (ref "T2")
      (value "BC847")
      (footprint "eagle-import:SOT23")
      (libsource (lib "eagle-import") (part "BC847"))
    )
    (comp (ref "T3")
      (value "BC847")
      (footprint "eagle-import:SOT23")
      (libsource (lib "eagle-import") (part "BC847"))
    )
    (comp (ref "T4")
      (value "DMN3150LW")
      (footprint "eagle-import:SOT323")
      (libsource (lib "eagle-import") (part "DMN3150LW"))
    )
    (comp (ref "T5")
      (value "DMN3150LW")
      (footprint "eagle-import:SOT323")
      (libsource (lib "eagle-import") (part "DMN3150LW"))
    )
    (comp (ref "T6")
      (value "DMN3150LW")
      (footprint "eagle-import:SOT323")
      (libsource (lib "eagle-import") (part "DMN3150LW"))
    )
    (comp (ref "T7")
      (value "DMN3150LW")
      (footprint "eagle-import:SOT323")
      (libsource (lib "eagle-import") (part "DMN3150LW"))
    )
    (comp (ref "T8")
      (value "DMN3150LW")
      (footprint "eagle-import:SOT323")
      (libsource (lib "eagle-import") (part "DMN3150LW"))
    )
    (comp (ref "U$8")
      (value "SSD1306")
      (footprint "eagle-import:30PINFPC_P0.7MM")
      (libsource (lib "eagle-import") (part "SSD1306"))
    )
    (comp (ref "U$9")
      (value "MLC7540")
      (footprint "eagle-import:MLC7540")
      (libsource (lib "eagle-import") (part "MLC7540"))
    )
    (comp (ref "U1")
      (value "ESP-WROOM-32")
      (footprint "eagle-import:ESP-WROOM-32")
      (libsource (lib "eagle-import") (part "ESP-WROOM-32"))
    )
    (comp (ref "UART")
      (value "CONN_04")
      (footprint "eagle-import:1X04")
      (libsource (lib "eagle-import") (part "CONN_04"))
    )
  )
  (nets
    (net (code "1") (name "2V") (class "Default")
      (node (ref "C10") (pin "1") (pinfunction "1_1") (pintype "passive"))
      (node (ref "C11") (pin "1") (pinfunction "1_1") (pintype "passive"))
      (node (ref "C12") (pin "1") (pinfunction "1_1") (pintype "passive"))
      (node (ref "C13") (pin "1") (pinfunction "1_1") (pintype "passive"))
      (node (ref "C14") (pin "1") (pinfunction "1_1") (pintype "passive"))
      (node (ref "C15") (pin "1") (pinfunction "1_1") (pintype "passive"))
      (node (ref "C16") (pin "1") (pinfunction "1_1") (pintype "passive"))
      (node (ref "C9") (pin "1") (pinfunction "1_1") (pintype "passive"))
      (node (ref "COUT1") (pin "1") (pinfunction "1_1") (pintype "passive"))
      (node (ref "L8") (pin "2") (pinfunction "2_2") (pintype "bidirectional"))
      (node (ref "LED1") (pin "2") (pinfunction "A_2") (pintype "bidirectional"))
      (node (ref "LED2") (pin "2") (pinfunction "A_2") (pintype "bidirectional"))
      (node (ref "LED3") (pin "2") (pinfunction "A_2") (pintype "bidirectional"))
      (node (ref "LED4") (pin "2") (pinfunction "A_2") (pintype "bidirectional"))
      (node (ref "RFBT8") (pin "2") (pinfunction "2_2") (pintype "passive"))
    )
    (net (code "2") (name "3V3") (class "Default")
      (node (ref "C19") (pin "1") (pinfunction "1_1") (pintype "passive"))
      (node (ref "C20") (pin "1") (pinfunction "1_1") (pintype "passive"))
      (node (ref "C21") (pin "1") (pinfunction "1_1") (pintype "passive"))
      (node (ref "C22") (pin "1") (pinfunction "1_1") (pintype "passive"))
      (node (ref "C23") (pin "1") (pinfunction "1_1") (pintype "passive"))
      (node (ref "C24") (pin "1") (pinfunction "1_1") (pintype "passive"))
      (node (ref "C25") (pin "1") (pinfunction "1_1") (pintype "passive"))
      (node (ref "C26") (pin "1") (pinfunction "1_1") (pintype "bidirectional"))
      (node (ref "C27") (pin "1") (pinfunction "1_1") (pintype "passive"))
      (node (ref "C29") (pin "1") (pinfunction "1_1") (pintype "passive"))
      (node (ref "C3") (pin "1") (pinfunction "1_1") (pintype "passive"))
      (node (ref "C30") (pin "1") (pinfunction "1_1") (pintype "passive"))
      (node (ref "C32") (pin "1") (pinfunction "1_1") (pintype "passive"))
      (node (ref "C4") (pin "1") (pinfunction "1_1") (pintype "passive"))
      (node (ref "COUT6") (pin "2") (pinfunction "2_2") (pintype "passive"))
      (node (ref "D4") (pin "1") (pinfunction "K_1") (pintype "bidirectional"))
      (node (ref "IC3") (pin "13") (pinfunction "VDD_13") (pintype "bidirectional"))
      (node (ref "IC3") (pin "8") (pinfunction "VDDIO_8") (pintype "bidirectional"))
      (node (ref "L6") (pin "2") (pinfunction "2_2") (pintype "bidirectional"))
      (node (ref "Q1") (pin "1") (pinfunction "C_1") (pintype "passive"))
      (node (ref "Q2") (pin "1") (pinfunction "C_1") (pintype "passive"))
      (node (ref "Q3") (pin "1") (pinfunction "C_1") (pintype "passive"))
      (node (ref "Q4") (pin "1") (pinfunction "C_1") (pintype "passive"))
      (node (ref "Q5") (pin "1") (pinfunction "C_1") (pintype "passive"))
      (node (ref "Q6") (pin "1") (pinfunction "C_1") (pintype "passive"))
      (node (ref "Q7") (pin "1") (pinfunction "C_1") (pintype "passive"))
      (node (ref "R2") (pin "2") (pinfunction "2_2") (pintype "passive"))
      (node (ref "R22") (pin "2") (pinfunction "2_2") (pintype "passive"))
      (node (ref "R29") (pin "2") (pinfunction "2_2") (pintype "passive"))
      (node (ref "R3") (pin "2") (pinfunction "2_2") (pintype "passive"))
      (node (ref "R30") (pin "2") (pinfunction "2_2") (pintype "passive"))
      (node (ref "R31") (pin "2") (pinfunction "2_2") (pintype "passive"))
      (node (ref "R35") (pin "2") (pinfunction "2_2") (pintype "passive"))
      (node (ref "R36") (pin "2") (pinfunction "2_2") (pintype "passive"))
      (node (ref "R52") (pin "2") (pinfunction "2_2") (pintype "passive"))
      (node (ref "R53") (pin "2") (pinfunction "2_2") (pintype "passive"))
      (node (ref "RFBT5") (pin "1") (pinfunction "1_1") (pintype "passive"))
      (node (ref "U$8") (pin "11") (pinfunction "BS1_11") (pintype "bidirectional"))
      (node (ref "U$8") (pin "6") (pinfunction "VBAT_6") (pintype "bidirectional"))
      (node (ref "U$8") (pin "9") (pinfunction "VDD_9") (pintype "bidirectional"))
      (node (ref "U1") (pin "2") (pinfunction "3V3_2") (pintype "bidirectional"))
      (node (ref "UART") (pin "1") (pinfunction "1_1") (pintype "passive"))
    )
    (net (code "3") (name "5V") (class "Default")
      (node (ref "C17") (pin "1") (pinfunction "1_1") (pintype "passive"))
      (node (ref "C18") (pin "1") (pinfunction "1_1") (pintype "passive"))
      (node (ref "COUT5") (pin "1") (pinfunction "1_1") (pintype "passive"))
      (node (ref "J5") (pin "3") (pinfunction "3_3") (pintype "bidirectional"))
      (node (ref "J6") (pin "3") (pinfunction "3_3") (pintype "bidirectional"))
      (node (ref "L5") (pin "1") (pinfunction "1_1") (pintype "bidirectional"))
      (node (ref "LED5") (pin "2") (pinfunction "A_2") (pintype "bidirectional"))
      (node (ref "RFTB5") (pin "2") (pinfunction "2_2") (pintype "passive"))
    )
    (net (code "4") (name "5V_FAN") (class "Default")
      (node (ref "C39") (pin "1") (pinfunction "1_1") (pintype "passive"))
      (node (ref "CIN3") (pin "1") (pinfunction "1_1") (pintype "passive"))
      (node (ref "D6") (pin "1") (pinfunction "K_1") (pintype "bidirectional"))
      (node (ref "J7") (pin "P$1") (pinfunction "P$1_P$1") (pintype "bidirectional"))
      (node (ref "L7") (pin "1") (pinfunction "1_1") (pintype "bidirectional"))
      (node (ref "RFBT6") (pin "2") (pinfunction "2_2") (pintype "passive"))
    )
    (net (code "5") (name "CB1") (class "Default")
      (node (ref "CBST1") (pin "1") (pinfunction "1_1") (pintype "passive"))
      (node (ref "PS2") (pin "1") (pinfunction "CB1_1") (pintype "output"))
    )
    (net (code "6") (name "CB2") (class "Default")
      (node (ref "CBST2") (pin "1") (pinfunction "1_1") (pintype "passive"))
      (node (ref "PS2") (pin "12") (pinfunction "CB2_12") (pintype "output"))
    )
    (net (code "7") (name "CB3") (class "Default")
      (node (ref "CBST3") (pin "2") (pinfunction "2_2") (pintype "passive"))
      (node (ref "PS2") (pin "28") (pinfunction "CB3_28") (pintype "output"))
    )
    (net (code "8") (name "CB4") (class "Default")
      (node (ref "CBST4") (pin "2") (pinfunction "2_2") (pintype "passive"))
      (node (ref "PS2") (pin "33") (pinfunction "CB4_33") (pintype "output"))
    )
    (net (code "9") (name "CS") (class "Default")
      (node (ref "IC3") (pin "22") (pinfunction "NCS_22") (pintype "bidirectional"))
      (node (ref "U1") (pin "11") (pinfunction "IO26_11") (pintype "bidirectional"))
    )
    (net (code "10") (name "EN") (class "Default")
      (node (ref "C28") (pin "1") (pinfunction "1_1") (pintype "passive"))
      (node (ref "R31") (pin "1") (pinfunction "1_1") (pintype "passive"))
      (node (ref "R38") (pin "2") (pinfunction "2_2") (pintype "passive"))
      (node (ref "U1") (pin "3") (pinfunction "EN_3") (pintype "bidirectional"))
    )
    (net (code "11") (name "FANPWM{slash}TMS") (class "Default")
      (node (ref "J3") (pin "1") (pinfunction "1_1") (pintype "passive"))
      (node (ref "J8") (pin "2") (pinfunction "2_2") (pintype "passive"))
      (node (ref "U1") (pin "13") (pinfunction "IO14_13") (pintype "bidirectional"))
    )
    (net (code "12") (name "FSYNC") (class "Default")
      (node (ref "IC3") (pin "11") (pinfunction "FSYNC_11") (pintype "bidirectional"))
    )
    (net (code "13") (name "F_RECEIVER") (class "Default")
      (node (ref "Q1") (pin "2") (pinfunction "E_2") (pintype "passive"))
      (node (ref "R14") (pin "2") (pinfunction "2_2") (pintype "passive"))
      (node (ref "U1") (pin "20") (pinfunction "CLK_20") (pintype "bidirectional"))
    )
    (net (code "14") (name "GND") (class "Default")
      (node (ref "C10") (pin "2") (pinfunction "2_2") (pintype "passive"))
      (node (ref "C11") (pin "2") (pinfunction "2_2") (pintype "passive"))
      (node (ref "C12") (pin "2") (pinfunction "2_2") (pintype "passive"))
      (node (ref "C13") (pin "2") (pinfunction "2_2") (pintype "passive"))
      (node (ref "C14") (pin "2") (pinfunction "2_2") (pintype "passive"))
      (node (ref "C15") (pin "2") (pinfunction "2_2") (pintype "passive"))
      (node (ref "C16") (pin "2") (pinfunction "2_2") (pintype "passive"))
      (node (ref "C17") (pin "2") (pinfunction "2_2") (pintype "passive"))
      (node (ref "C18") (pin "2") (pinfunction "2_2") (pintype "passive"))
      (node (ref "C19") (pin "2") (pinfunction "2_2") (pintype "passive"))
      (node (ref "C2") (pin "2") (pinfunction "2_2") (pintype "passive"))
      (node (ref "C20") (pin "2") (pinfunction "2_2") (pintype "passive"))
      (node (ref "C21") (pin "2") (pinfunction "2_2") (pintype "passive"))
      (node (ref "C22") (pin "2") (pinfunction "2_2") (pintype "passive"))
      (node (ref "C23") (pin "2") (pinfunction "2_2") (pintype "passive"))
      (node (ref "C24") (pin "2") (pinfunction "2_2") (pintype "passive"))
      (node (ref "C25") (pin "2") (pinfunction "2_2") (pintype "passive"))
      (node (ref "C26") (pin "2") (pinfunction "2_2") (pintype "bidirectional"))
      (node (ref "C27") (pin "2") (pinfunction "2_2") (pintype "passive"))
      (node (ref "C28") (pin "2") (pinfunction "2_2") (pintype "passive"))
      (node (ref "C29") (pin "2") (pinfunction "2_2") (pintype "passive"))
      (node (ref "C3") (pin "2") (pinfunction "2_2") (pintype "passive"))
      (node (ref "C30") (pin "2") (pinfunction "2_2") (pintype "passive"))
      (node (ref "C31") (pin "2") (pinfunction "2_2") (pintype "passive"))
      (node (ref "C32") (pin "2") (pinfunction "2_2") (pintype "passive"))
      (node (ref "C33") (pin "2") (pinfunction "2_2") (pintype "passive"))
      (node (ref "C34") (pin "2") (pinfunction "2_2") (pintype "passive"))
      (node (ref "C35") (pin "2") (pinfunction "2_2") (pintype "passive"))
      (node (ref "C36") (pin "2") (pinfunction "2_2") (pintype "passive"))
      (node (ref "C37") (pin "2") (pinfunction "2_2") (pintype "passive"))
      (node (ref "C38") (pin "2") (pinfunction "2_2") (pintype "passive"))
      (node (ref "C39") (pin "2") (pinfunction "2_2") (pintype "passive"))
      (node (ref "C4") (pin "2") (pinfunction "2_2") (pintype "passive"))
      (node (ref "C40") (pin "2") (pinfunction "2_2") (pintype "passive"))
      (node (ref "C43") (pin "1") (pinfunction "1_1") (pintype "passive"))
      (node (ref "C44") (pin "1") (pinfunction "1_1") (pintype "passive"))
      (node (ref "C45") (pin "2") (pinfunction "2_2") (pintype "passive"))
      (node (ref "C46") (pin "2") (pinfunction "2_2") (pintype "passive"))
      (node (ref "C47") (pin "2") (pinfunction "2_2") (pintype "passive"))
      (node (ref "C48") (pin "2") (pinfunction "2_2") (pintype "passive"))
      (node (ref "C49") (pin "2") (pinfunction "2_2") (pintype "passive"))
      (node (ref "C5") (pin "2") (pinfunction "2_2") (pintype "passive"))
      (node (ref "C50") (pin "2") (pinfunction "2_2") (pintype "passive"))
      (node (ref "C6") (pin "2") (pinfunction "2_2") (pintype "passive"))
      (node (ref "C7") (pin "2") (pinfunction "2_2") (pintype "passive"))
      (node (ref "C8") (pin "1") (pinfunction "1_1") (pintype "passive"))
      (node (ref "C9") (pin "2") (pinfunction "2_2") (pintype "passive"))
      (node (ref "CCOMP10") (pin "2") (pinfunction "2_2") (pintype "passive"))
      (node (ref "CCOMP11") (pin "1") (pinfunction "1_1") (pintype "passive"))
      (node (ref "CCOMP13") (pin "1") (pinfunction "1_1") (pintype "passive"))
      (node (ref "CCOMP5") (pin "2") (pinfunction "2_2") (pintype "passive"))
      (node (ref "CCOMP6") (pin "2") (pinfunction "2_2") (pintype "passive"))
      (node (ref "CCOMP7") (pin "2") (pinfunction "2_2") (pintype "passive"))
      (node (ref "CCOMP8") (pin "1") (pinfunction "1_1") (pintype "passive"))
      (node (ref "CCOMP9") (pin "1") (pinfunction "1_1") (pintype "passive"))
      (node (ref "CIN1") (pin "2") (pinfunction "2_2") (pintype "passive"))
      (node (ref "CIN2") (pin "2") (pinfunction "2_2") (pintype "passive"))
      (node (ref "CIN3") (pin "2") (pinfunction "2_2") (pintype "passive"))
      (node (ref "COUT1") (pin "2") (pinfunction "2_2") (pintype "passive"))
      (node (ref "COUT5") (pin "2") (pinfunction "2_2") (pintype "passive"))
      (node (ref "COUT6") (pin "1") (pinfunction "1_1") (pintype "passive"))
      (node (ref "CSS5") (pin "2") (pinfunction "2_2") (pintype "passive"))
      (node (ref "CSS6") (pin "2") (pinfunction "2_2") (pintype "passive"))
      (node (ref "CSS7") (pin "2") (pinfunction "2_2") (pintype "passive"))
      (node (ref "CSS8") (pin "1") (pinfunction "1_1") (pintype "passive"))
      (node (ref "CVDD1") (pin "2") (pinfunction "2_2") (pintype "passive"))
      (node (ref "CVDDA1") (pin "1") (pinfunction "1_1") (pintype "passive"))
      (node (ref "CVDDG1") (pin "2") (pinfunction "2_2") (pintype "passive"))
      (node (ref "IC1") (pin "11") (pinfunction "NC_1_11") (pintype "bidirectional"))
      (node (ref "IC1") (pin "12") (pinfunction "NC_2_12") (pintype "bidirectional"))
      (node (ref "IC1") (pin "20") (pinfunction "AGND_20") (pintype "bidirectional"))
      (node (ref "IC1") (pin "21") (pinfunction "PGND_21") (pintype "bidirectional"))
      (node (ref "IC3") (pin "18") (pinfunction "GND_18") (pintype "bidirectional"))
      (node (ref "IC3") (pin "25") (pinfunction "PAD_25") (pintype "bidirectional"))
      (node (ref "IC6") (pin "3") (pinfunction "GND_3") (pintype "bidirectional"))
      (node (ref "IC8") (pin "3") (pinfunction "GND_3") (pintype "bidirectional"))
      (node (ref "IC9") (pin "4") (pinfunction "INB_4") (pintype "bidirectional"))
      (node (ref "J2") (pin "P$2") (pinfunction "P$2_P$2") (pintype "bidirectional"))
      (node (ref "J5") (pin "4") (pinfunction "4_4") (pintype "bidirectional"))
      (node (ref "J6") (pin "4") (pinfunction "4_4") (pintype "bidirectional"))
      (node (ref "PB1") (pin "1") (pinfunction "1_1") (pintype "passive"))
      (node (ref "PB2") (pin "1") (pinfunction "1_1") (pintype "passive"))
      (node (ref "PS2") (pin "21") (pinfunction "AGND_21") (pintype "power_in"))
      (node (ref "PS2") (pin "49") (pinfunction "PGND_49") (pintype "power_in"))
      (node (ref "PS2") (pin "7") (pinfunction "PGND1_7") (pintype "power_in"))
      (node (ref "PS2") (pin "8") (pinfunction "PGND2_8") (pintype "power_in"))
      (node (ref "Q10") (pin "3") (pinfunction "N1S/N2S_3") (pintype "bidirectional"))
      (node (ref "Q11") (pin "3") (pinfunction "N1S/N2S_3") (pintype "bidirectional"))
      (node (ref "R1") (pin "1") (pinfunction "1_1") (pintype "passive"))
      (node (ref "R11") (pin "1") (pinfunction "1_1") (pintype "passive"))
      (node (ref "R13") (pin "1") (pinfunction "1_1") (pintype "passive"))
      (node (ref "R14") (pin "1") (pinfunction "1_1") (pintype "passive"))
      (node (ref "R15") (pin "1") (pinfunction "1_1") (pintype "passive"))
      (node (ref "R16") (pin "1") (pinfunction "1_1") (pintype "passive"))
      (node (ref "R17") (pin "1") (pinfunction "1_1") (pintype "passive"))
      (node (ref "R18") (pin "1") (pinfunction "1_1") (pintype "passive"))
      (node (ref "R19") (pin "1") (pinfunction "1_1") (pintype "passive"))
      (node (ref "R20") (pin "1") (pinfunction "1_1") (pintype "passive"))
      (node (ref "R23") (pin "1") (pinfunction "1_1") (pintype "passive"))
      (node (ref "R24") (pin "1") (pinfunction "1_1") (pintype "passive"))
      (node (ref "R26") (pin "1") (pinfunction "1_1") (pintype "passive"))
      (node (ref "R45") (pin "1") (pinfunction "1_1") (pintype "passive"))
      (node (ref "R6") (pin "1") (pinfunction "1_1") (pintype "passive"))
      (node (ref "R8") (pin "1") (pinfunction "1_1") (pintype "passive"))
      (node (ref "R9") (pin "1") (pinfunction "1_1") (pintype "passive"))
      (node (ref "RFBB5") (pin "1") (pinfunction "1_1") (pintype "passive"))
      (node (ref "RFBB6") (pin "1") (pinfunction "1_1") (pintype "passive"))
      (node (ref "RFBB7") (pin "2") (pinfunction "2_2") (pintype "passive"))
      (node (ref "RFBB8") (pin "1") (pinfunction "1_1") (pintype "passive"))
      (node (ref "ROSC1") (pin "1") (pinfunction "1_1") (pintype "passive"))
      (node (ref "RPMU7") (pin "2") (pinfunction "2_2") (pintype "passive"))
      (node (ref "T1") (pin "1") (pinfunction "S_1") (pintype "passive"))
      (node (ref "T1") (pin "2") (pinfunction "S_2") (pintype "passive"))
      (node (ref "T1") (pin "3") (pinfunction "S_3") (pintype "passive"))
      (node (ref "T2") (pin "2") (pinfunction "E_2") (pintype "passive"))
      (node (ref "T3") (pin "2") (pinfunction "E_2") (pintype "passive"))
      (node (ref "T4") (pin "S") (pinfunction "S_S") (pintype "passive"))
      (node (ref "T5") (pin "S") (pinfunction "S_S") (pintype "passive"))
      (node (ref "T6") (pin "S") (pinfunction "S_S") (pintype "passive"))
      (node (ref "T7") (pin "S") (pinfunction "S_S") (pintype "passive"))
      (node (ref "T8") (pin "S") (pinfunction "S_S") (pintype "passive"))
      (node (ref "U$8") (pin "1") (pinfunction "NC_1_1") (pintype "bidirectional"))
      (node (ref "U$8") (pin "10") (pinfunction "BS0_10") (pintype "bidirectional"))
      (node (ref "U$8") (pin "12") (pinfunction "BS2_12") (pintype "bidirectional"))
      (node (ref "U$8") (pin "13") (pinfunction "CS#_13") (pintype "bidirectional"))
      (node (ref "U$8") (pin "16") (pinfunction "R/W#_16") (pintype "bidirectional"))
      (node (ref "U$8") (pin "17") (pinfunction "E/RD#_17") (pintype "bidirectional"))
      (node (ref "U$8") (pin "21") (pinfunction "D3_21") (pintype "bidirectional"))
      (node (ref "U$8") (pin "22") (pinfunction "D4_22") (pintype "bidirectional"))
      (node (ref "U$8") (pin "23") (pinfunction "D5_23") (pintype "bidirectional"))
      (node (ref "U$8") (pin "24") (pinfunction "D6_24") (pintype "bidirectional"))
      (node (ref "U$8") (pin "25") (pinfunction "D7_25") (pintype "bidirectional"))
      (node (ref "U$8") (pin "29") (pinfunction "VLSS_29") (pintype "bidirectional"))
      (node (ref "U$8") (pin "30") (pinfunction "NC_3_30") (pintype "bidirectional"))
      (node (ref "U$8") (pin "8") (pinfunction "VSS_8") (pintype "bidirectional"))
      (node (ref "U1") (pin "1") (pinfunction "GND_1") (pintype "bidirectional"))
      (node (ref "U1") (pin "15") (pinfunction "GND_15") (pintype "bidirectional"))
      (node (ref "U1") (pin "38") (pinfunction "GND_38") (pintype "bidirectional"))
      (node (ref "U1") (pin "GND") (pinfunction "GND_GND") (pintype "bidirectional"))
      (node (ref "UART") (pin "2") (pinfunction "2_2") (pintype "passive"))
    )
    (net (code "15") (name "I2CALERT") (class "Default")
      (node (ref "PS2") (pin "41") (pinfunction "I2CALERT_41") (pintype "output"))
      (node (ref "RPMU8") (pin "1") (pinfunction "1_1") (pintype "passive"))
    )
    (net (code "16") (name "INT") (class "Default")
      (node (ref "IC3") (pin "12") (pinfunction "INT_12") (pintype "bidirectional"))
    )
    (net (code "17") (name "IO0") (class "Default")
      (node (ref "R22") (pin "1") (pinfunction "1_1") (pintype "passive"))
      (node (ref "R37") (pin "2") (pinfunction "2_2") (pintype "passive"))
      (node (ref "U1") (pin "25") (pinfunction "IO0_25") (pintype "bidirectional"))
    )
    (net (code "18") (name "IO2") (class "Default")
      (node (ref "R23") (pin "2") (pinfunction "2_2") (pintype "passive"))
      (node (ref "U1") (pin "24") (pinfunction "IO2_24") (pintype "bidirectional"))
    )
    (net (code "19") (name "LF_EMITTER{slash}TCK") (class "Default")
      (node (ref "JTAG") (pin "2") (pinfunction "2_2") (pintype "passive"))
      (node (ref "R11") (pin "2") (pinfunction "2_2") (pintype "passive"))
      (node (ref "T5") (pin "G") (pinfunction "G_G") (pintype "passive"))
      (node (ref "U1") (pin "16") (pinfunction "IO13_16") (pintype "bidirectional"))
    )
    (net (code "20") (name "LF_RECEIVER") (class "Default")
      (node (ref "Q4") (pin "2") (pinfunction "E_2") (pintype "passive"))
      (node (ref "R17") (pin "2") (pinfunction "2_2") (pintype "passive"))
      (node (ref "U1") (pin "26") (pinfunction "IO4_26") (pintype "bidirectional"))
    )
    (net (code "21") (name "LPWMA") (class "Default")
      (node (ref "IC8") (pin "2") (pinfunction "INA_2") (pintype "bidirectional"))
      (node (ref "R52") (pin "1") (pinfunction "1_1") (pintype "passive"))
      (node (ref "U1") (pin "31") (pinfunction "IO19_31") (pintype "bidirectional"))
    )
    (net (code "22") (name "LPWMB") (class "Default")
      (node (ref "IC8") (pin "4") (pinfunction "INB_4") (pintype "bidirectional"))
      (node (ref "R53") (pin "1") (pinfunction "1_1") (pintype "passive"))
      (node (ref "U1") (pin "30") (pinfunction "IO18_30") (pintype "bidirectional"))
    )
    (net (code "23") (name "L_EMITTER") (class "Default")
      (node (ref "R8") (pin "2") (pinfunction "2_2") (pintype "passive"))
      (node (ref "T4") (pin "G") (pinfunction "G_G") (pintype "passive"))
      (node (ref "U1") (pin "36") (pinfunction "IO22_36") (pintype "bidirectional"))
    )
    (net (code "24") (name "L_ENC_A") (class "Default")
      (node (ref "J6") (pin "1") (pinfunction "1_1") (pintype "bidirectional"))
      (node (ref "U1") (pin "5") (pinfunction "SENSOR_VN_5") (pintype "input"))
    )
    (net (code "25") (name "L_ENC_B") (class "Default")
      (node (ref "J6") (pin "2") (pinfunction "2_2") (pintype "bidirectional"))
      (node (ref "U1") (pin "4") (pinfunction "SENSOR_VP_4") (pintype "input"))
    )
    (net (code "26") (name "L_RECEIVER1") (class "Default")
      (node (ref "Q2") (pin "2") (pinfunction "E_2") (pintype "passive"))
      (node (ref "R15") (pin "2") (pinfunction "2_2") (pintype "passive"))
      (node (ref "U1") (pin "22") (pinfunction "SD1_22") (pintype "bidirectional"))
    )
    (net (code "27") (name "L_RECEIVER2") (class "Default")
      (node (ref "Q3") (pin "2") (pinfunction "E_2") (pintype "passive"))
      (node (ref "R16") (pin "2") (pinfunction "2_2") (pintype "passive"))
      (node (ref "U1") (pin "21") (pinfunction "SDO_21") (pintype "bidirectional"))
    )
    (net (code "28") (name "M_EMITTER{slash}TDO") (class "Default")
      (node (ref "JTAG") (pin "1") (pinfunction "1_1") (pintype "passive"))
      (node (ref "R13") (pin "2") (pinfunction "2_2") (pintype "passive"))
      (node (ref "T6") (pin "G") (pinfunction "G_G") (pintype "passive"))
      (node (ref "U1") (pin "23") (pinfunction "IO15_23") (pintype "bidirectional"))
    )
    (net (code "29") (name "Net-(C2-Pad1)") (class "Default")
      (node (ref "C2") (pin "1") (pinfunction "1_1") (pintype "passive"))
      (node (ref "R21") (pin "1") (pinfunction "1_1") (pintype "passive"))
    )
    (net (code "30") (name "Net-(C43-Pad2)") (class "Default")
      (node (ref "C43") (pin "2") (pinfunction "2_2") (pintype "passive"))
      (node (ref "PB1") (pin "2") (pinfunction "2_2") (pintype "passive"))
      (node (ref "R37") (pin "1") (pinfunction "1_1") (pintype "passive"))
    )
    (net (code "31") (name "Net-(C44-Pad2)") (class "Default")
      (node (ref "C44") (pin "2") (pinfunction "2_2") (pintype "passive"))
      (node (ref "PB2") (pin "2") (pinfunction "2_2") (pintype "passive"))
      (node (ref "R38") (pin "1") (pinfunction "1_1") (pintype "passive"))
    )
    (net (code "32") (name "Net-(CCOMP6-Pad1)") (class "Default")
      (node (ref "CCOMP6") (pin "1") (pinfunction "1_1") (pintype "passive"))
      (node (ref "RCOMP7") (pin "1") (pinfunction "1_1") (pintype "passive"))
    )
    (net (code "33") (name "Net-(CCOMP8-Pad2)") (class "Default")
      (node (ref "CCOMP8") (pin "2") (pinfunction "2_2") (pintype "passive"))
      (node (ref "RCOMP6") (pin "1") (pinfunction "1_1") (pintype "passive"))
    )
    (net (code "34") (name "Net-(CCOMP9-Pad2)") (class "Default")
      (node (ref "CCOMP9") (pin "2") (pinfunction "2_2") (pintype "passive"))
      (node (ref "RCOMP8") (pin "2") (pinfunction "2_2") (pintype "passive"))
    )
    (net (code "35") (name "Net-(CCOMP11-Pad2)") (class "Default")
      (node (ref "CCOMP11") (pin "2") (pinfunction "2_2") (pintype "passive"))
      (node (ref "RCOMP5") (pin "2") (pinfunction "2_2") (pintype "passive"))
    )
    (net (code "36") (name "Net-(D3-PadC)") (class "Default")
      (node (ref "D3") (pin "C") (pinfunction "C_C") (pintype "passive"))
      (node (ref "R48") (pin "2") (pinfunction "2_2") (pintype "passive"))
    )
    (net (code "37") (name "Net-(D4-A)") (class "Default")
      (node (ref "D4") (pin "2") (pinfunction "A_2") (pintype "bidirectional"))
      (node (ref "R35") (pin "1") (pinfunction "1_1") (pintype "passive"))
      (node (ref "U$8") (pin "14") (pinfunction "RES#_14") (pintype "bidirectional"))
    )
    (net (code "38") (name "Net-(D5-PadC)") (class "Default")
      (node (ref "D5") (pin "C") (pinfunction "C_C") (pintype "passive"))
      (node (ref "R49") (pin "2") (pinfunction "2_2") (pintype "passive"))
    )
    (net (code "39") (name "Net-(D6-A)") (class "Default")
      (node (ref "D6") (pin "2") (pinfunction "A_2") (pintype "bidirectional"))
      (node (ref "J7") (pin "P$2") (pinfunction "P$2_P$2") (pintype "bidirectional"))
      (node (ref "T1") (pin "MB") (pinfunction "D_MB") (pintype "passive"))
    )
    (net (code "40") (name "Net-(IC1-BOOT)") (class "Default")
      (node (ref "C1") (pin "1") (pinfunction "1_1") (pintype "passive"))
      (node (ref "IC1") (pin "8") (pinfunction "BOOT_8") (pintype "bidirectional"))
    )
    (net (code "41") (name "Net-(IC1-COMP)") (class "Default")
      (node (ref "C5") (pin "1") (pinfunction "1_1") (pintype "passive"))
      (node (ref "IC1") (pin "18") (pinfunction "COMP_18") (pintype "bidirectional"))
      (node (ref "R21") (pin "2") (pinfunction "2_2") (pintype "passive"))
    )
    (net (code "42") (name "Net-(IC1-FB)") (class "Default")
      (node (ref "IC1") (pin "17") (pinfunction "FB_17") (pintype "bidirectional"))
      (node (ref "R24") (pin "2") (pinfunction "2_2") (pintype "passive"))
      (node (ref "R25") (pin "1") (pinfunction "1_1") (pintype "passive"))
    )
    (net (code "43") (name "Net-(IC1-FSW)") (class "Default")
      (node (ref "IC1") (pin "3") (pinfunction "FSW_3") (pintype "bidirectional"))
      (node (ref "R27") (pin "1") (pinfunction "1_1") (pintype "passive"))
    )
    (net (code "44") (name "Net-(IC1-ILIM)") (class "Default")
      (node (ref "IC1") (pin "19") (pinfunction "ILIM_19") (pintype "bidirectional"))
      (node (ref "R26") (pin "2") (pinfunction "2_2") (pintype "passive"))
    )
    (net (code "45") (name "Net-(IC1-SS)") (class "Default")
      (node (ref "C47") (pin "1") (pinfunction "1_1") (pintype "passive"))
      (node (ref "IC1") (pin "10") (pinfunction "SS_10") (pintype "bidirectional"))
    )
    (net (code "46") (name "Net-(IC1-SW_1)") (class "Default")
      (node (ref "C1") (pin "2") (pinfunction "2_2") (pintype "passive"))
      (node (ref "IC1") (pin "4") (pinfunction "SW_1_4") (pintype "bidirectional"))
      (node (ref "IC1") (pin "5") (pinfunction "SW_2_5") (pintype "bidirectional"))
      (node (ref "IC1") (pin "6") (pinfunction "SW_3_6") (pintype "bidirectional"))
      (node (ref "IC1") (pin "7") (pinfunction "SW_4_7") (pintype "bidirectional"))
      (node (ref "R27") (pin "2") (pinfunction "2_2") (pintype "passive"))
      (node (ref "U$9") (pin "P$2") (pinfunction "2_P$2") (pintype "bidirectional"))
    )
    (net (code "47") (name "Net-(IC1-VCC)") (class "Default")
      (node (ref "C48") (pin "1") (pinfunction "1_1") (pintype "passive"))
      (node (ref "IC1") (pin "1") (pinfunction "VCC_1") (pintype "bidirectional"))
    )
    (net (code "48") (name "Net-(IC3-REGOUT)") (class "Default")
      (node (ref "C31") (pin "1") (pinfunction "1_1") (pintype "passive"))
      (node (ref "IC3") (pin "10") (pinfunction "REGOUT_10") (pintype "bidirectional"))
    )
    (net (code "49") (name "Net-(IC6-OUTA)") (class "Default")
      (node (ref "IC6") (pin "7") (pinfunction "OUTA_7") (pintype "bidirectional"))
      (node (ref "Q10") (pin "1") (pinfunction "N1G_1") (pintype "bidirectional"))
      (node (ref "Q10") (pin "8") (pinfunction "P1G_8") (pintype "bidirectional"))
    )
    (net (code "50") (name "Net-(IC6-OUTB)") (class "Default")
      (node (ref "IC6") (pin "5") (pinfunction "OUTB_5") (pintype "bidirectional"))
      (node (ref "Q10") (pin "4") (pinfunction "N2G_4") (pintype "bidirectional"))
      (node (ref "Q10") (pin "5") (pinfunction "P2G_5") (pintype "bidirectional"))
    )
    (net (code "51") (name "Net-(IC8-OUTA)") (class "Default")
      (node (ref "IC8") (pin "7") (pinfunction "OUTA_7") (pintype "bidirectional"))
      (node (ref "Q11") (pin "1") (pinfunction "N1G_1") (pintype "bidirectional"))
      (node (ref "Q11") (pin "8") (pinfunction "P1G_8") (pintype "bidirectional"))
    )
    (net (code "52") (name "Net-(IC8-OUTB)") (class "Default")
      (node (ref "IC8") (pin "5") (pinfunction "OUTB_5") (pintype "bidirectional"))
      (node (ref "Q11") (pin "4") (pinfunction "N2G_4") (pintype "bidirectional"))
      (node (ref "Q11") (pin "5") (pinfunction "P2G_5") (pintype "bidirectional"))
    )
    (net (code "53") (name "Net-(IC9-GND)") (class "Default")
      (node (ref "IC9") (pin "3") (pinfunction "GND_3") (pintype "bidirectional"))
      (node (ref "J8") (pin "1") (pinfunction "1_1") (pintype "passive"))
      (node (ref "R36") (pin "1") (pinfunction "1_1") (pintype "passive"))
    )
    (net (code "54") (name "Net-(IC9-VDD)") (class "Default")
      (node (ref "IC9") (pin "6") (pinfunction "VDD_6") (pintype "bidirectional"))
      (node (ref "T1") (pin "4") (pinfunction "G_4") (pintype "passive"))
    )
    (net (code "55") (name "Net-(LED1-K)") (class "Default")
      (node (ref "LED1") (pin "1") (pinfunction "K_1") (pintype "bidirectional"))
      (node (ref "R4") (pin "2") (pinfunction "2_2") (pintype "passive"))
    )
    (net (code "56") (name "Net-(LED2-K)") (class "Default")
      (node (ref "LED2") (pin "1") (pinfunction "K_1") (pintype "bidirectional"))
      (node (ref "R5") (pin "2") (pinfunction "2_2") (pintype "passive"))
    )
    (net (code "57") (name "Net-(LED3-K)") (class "Default")
      (node (ref "LED3") (pin "1") (pinfunction "K_1") (pintype "bidirectional"))
      (node (ref "R7") (pin "2") (pinfunction "2_2") (pintype "passive"))
    )
    (net (code "58") (name "Net-(LED4-K)") (class "Default")
      (node (ref "LED4") (pin "1") (pinfunction "K_1") (pintype "bidirectional"))
      (node (ref "R10") (pin "2") (pinfunction "2_2") (pintype "passive"))
    )
    (net (code "59") (name "Net-(LED5-K)") (class "Default")
      (node (ref "LED5") (pin "1") (pinfunction "K_1") (pintype "bidirectional"))
      (node (ref "LED7") (pin "2") (pinfunction "A_2") (pintype "bidirectional"))
    )
    (net (code "60") (name "Net-(LED7-K)") (class "Default")
      (node (ref "LED7") (pin "1") (pinfunction "K_1") (pintype "bidirectional"))
      (node (ref "R12") (pin "2") (pinfunction "2_2") (pintype "passive"))
    )
    (net (code "61") (name "Net-(PLZ6V2B-G3/H-PadA)") (class "Default")
      (node (ref "PLZ6V2B-G3/H") (pin "A") (pinfunction "A_A") (pintype "bidirectional"))
      (node (ref "R45") (pin "2") (pinfunction "2_2") (pintype "passive"))
      (node (ref "R46") (pin "1") (pinfunction "1_1") (pintype "passive"))
    )
    (net (code "62") (name "Net-(PS2-COMP1)") (class "Default")
      (node (ref "CCOMP13") (pin "2") (pinfunction "2_2") (pintype "passive"))
      (node (ref "PS2") (pin "46") (pinfunction "COMP1_46") (pintype "input"))
      (node (ref "RCOMP5") (pin "1") (pinfunction "1_1") (pintype "passive"))
    )
    (net (code "63") (name "Net-(PS2-COMP2)") (class "Default")
      (node (ref "CCOMP5") (pin "1") (pinfunction "1_1") (pintype "passive"))
      (node (ref "PS2") (pin "15") (pinfunction "COMP2_15") (pintype "input"))
      (node (ref "RCOMP6") (pin "2") (pinfunction "2_2") (pintype "passive"))
    )
    (net (code "64") (name "Net-(PS2-COMP3)") (class "Default")
      (node (ref "CCOMP7") (pin "1") (pinfunction "1_1") (pintype "passive"))
      (node (ref "PS2") (pin "25") (pinfunction "COMP3_25") (pintype "input"))
      (node (ref "RCOMP7") (pin "2") (pinfunction "2_2") (pintype "passive"))
    )
    (net (code "65") (name "Net-(PS2-COMP4)") (class "Default")
      (node (ref "CCOMP10") (pin "1") (pinfunction "1_1") (pintype "passive"))
      (node (ref "PS2") (pin "36") (pinfunction "COMP4_36") (pintype "input"))
      (node (ref "RCOMP8") (pin "1") (pinfunction "1_1") (pintype "passive"))
    )
    (net (code "66") (name "Net-(PS2-I2CADDR)") (class "Default")
      (node (ref "PS2") (pin "38") (pinfunction "I2CADDR_38") (pintype "input"))
      (node (ref "RPMU7") (pin "1") (pinfunction "1_1") (pintype "passive"))
    )
    (net (code "67") (name "Net-(PS2-RCLOCK)") (class "Default")
      (node (ref "PS2") (pin "40") (pinfunction "RCLOCK_40") (pintype "input"))
      (node (ref "ROSC1") (pin "2") (pinfunction "2_2") (pintype "passive"))
    )
    (net (code "68") (name "Net-(PS2-SS1{slash}PG1)") (class "Default")
      (node (ref "CSS8") (pin "2") (pinfunction "2_2") (pintype "passive"))
      (node (ref "PS2") (pin "45") (pinfunction "SS1/PG1_45") (pintype "input"))
    )
    (net (code "69") (name "Net-(PS2-SS2{slash}PG2)") (class "Default")
      (node (ref "CSS5") (pin "1") (pinfunction "1_1") (pintype "passive"))
      (node (ref "PS2") (pin "16") (pinfunction "SS2/PG2_16") (pintype "input"))
    )
    (net (code "70") (name "Net-(PS2-SS3{slash}PG3)") (class "Default")
      (node (ref "CSS6") (pin "1") (pinfunction "1_1") (pintype "passive"))
      (node (ref "PS2") (pin "24") (pinfunction "SS3/PG3_24") (pintype "input"))
    )
    (net (code "71") (name "Net-(PS2-SS4{slash}PG4)") (class "Default")
      (node (ref "CSS7") (pin "1") (pinfunction "1_1") (pintype "passive"))
      (node (ref "PS2") (pin "37") (pinfunction "SS4/PG4_37") (pintype "input"))
    )
    (net (code "72") (name "Net-(PS2-SW1_1)") (class "Default")
      (node (ref "CBST1") (pin "2") (pinfunction "2_2") (pintype "passive"))
      (node (ref "L7") (pin "2") (pinfunction "2_2") (pintype "bidirectional"))
      (node (ref "PS2") (pin "2") (pinfunction "SW1_1_2") (pintype "output"))
      (node (ref "PS2") (pin "3") (pinfunction "SW1_2_3") (pintype "output"))
      (node (ref "PS2") (pin "4") (pinfunction "SW1_3_4") (pintype "output"))
    )
    (net (code "73") (name "Net-(PS2-VDDA)") (class "Default")
      (node (ref "CVDDA1") (pin "2") (pinfunction "2_2") (pintype "passive"))
      (node (ref "PS2") (pin "19") (pinfunction "VDDA_19") (pintype "output"))
    )
    (net (code "74") (name "Net-(PS2-VDDG)") (class "Default")
      (node (ref "CVDDG1") (pin "1") (pinfunction "1_1") (pintype "passive"))
      (node (ref "PS2") (pin "18") (pinfunction "VDDG_18") (pintype "input"))
    )
    (net (code "75") (name "Net-(PS2-VFB1)") (class "Default")
      (node (ref "PS2") (pin "47") (pinfunction "VFB1_47") (pintype "input"))
      (node (ref "RFBB8") (pin "2") (pinfunction "2_2") (pintype "passive"))
      (node (ref "RFBT6") (pin "1") (pinfunction "1_1") (pintype "passive"))
    )
    (net (code "76") (name "Net-(PS2-VFB2)") (class "Default")
      (node (ref "PS2") (pin "14") (pinfunction "VFB2_14") (pintype "input"))
      (node (ref "RFBB5") (pin "2") (pinfunction "2_2") (pintype "passive"))
      (node (ref "RFTB5") (pin "1") (pinfunction "1_1") (pintype "passive"))
    )
    (net (code "77") (name "Net-(PS2-VFB3)") (class "Default")
      (node (ref "PS2") (pin "26") (pinfunction "VFB3_26") (pintype "input"))
      (node (ref "RFBB6") (pin "2") (pinfunction "2_2") (pintype "passive"))
      (node (ref "RFBT8") (pin "1") (pinfunction "1_1") (pintype "passive"))
    )
    (net (code "78") (name "Net-(PS2-VFB4)") (class "Default")
      (node (ref "PS2") (pin "35") (pinfunction "VFB4_35") (pintype "input"))
      (node (ref "RFBB7") (pin "1") (pinfunction "1_1") (pintype "passive"))
      (node (ref "RFBT5") (pin "2") (pinfunction "2_2") (pintype "passive"))
    )
    (net (code "79") (name "Net-(Q10-N1D{slash}P1D)") (class "Default")
      (node (ref "J5") (pin "5") (pinfunction "5_5") (pintype "bidirectional"))
      (node (ref "Q10") (pin "2") (pinfunction "N1D/P1D_2") (pintype "bidirectional"))
    )
    (net (code "80") (name "Net-(Q10-N2D{slash}P2D)") (class "Default")
      (node (ref "J5") (pin "6") (pinfunction "6_6") (pintype "bidirectional"))
      (node (ref "Q10") (pin "6") (pinfunction "N2D/P2D_6") (pintype "bidirectional"))
    )
    (net (code "81") (name "Net-(Q11-N1D{slash}P1D)") (class "Default")
      (node (ref "J6") (pin "5") (pinfunction "5_5") (pintype "bidirectional"))
      (node (ref "Q11") (pin "2") (pinfunction "N1D/P1D_2") (pintype "bidirectional"))
    )
    (net (code "82") (name "Net-(Q11-N2D{slash}P2D)") (class "Default")
      (node (ref "J6") (pin "6") (pinfunction "6_6") (pintype "bidirectional"))
      (node (ref "Q11") (pin "6") (pinfunction "N2D/P2D_6") (pintype "bidirectional"))
    )
    (net (code "83") (name "Net-(R4-Pad1)") (class "Default")
      (node (ref "R4") (pin "1") (pinfunction "1_1") (pintype "passive"))
      (node (ref "T8") (pin "D") (pinfunction "D_D") (pintype "passive"))
    )
    (net (code "84") (name "Net-(R5-Pad1)") (class "Default")
      (node (ref "R5") (pin "1") (pinfunction "1_1") (pintype "passive"))
      (node (ref "T4") (pin "D") (pinfunction "D_D") (pintype "passive"))
    )
    (net (code "85") (name "Net-(R7-Pad1)") (class "Default")
      (node (ref "R7") (pin "1") (pinfunction "1_1") (pintype "passive"))
      (node (ref "T7") (pin "D") (pinfunction "D_D") (pintype "passive"))
    )
    (net (code "86") (name "Net-(R10-Pad1)") (class "Default")
      (node (ref "R10") (pin "1") (pinfunction "1_1") (pintype "passive"))
      (node (ref "T5") (pin "D") (pinfunction "D_D") (pintype "passive"))
    )
    (net (code "87") (name "Net-(R12-Pad1)") (class "Default")
      (node (ref "R12") (pin "1") (pinfunction "1_1") (pintype "passive"))
      (node (ref "T6") (pin "D") (pinfunction "D_D") (pintype "passive"))
    )
    (net (code "88") (name "Net-(T2-B)") (class "Default")
      (node (ref "R46") (pin "2") (pinfunction "2_2") (pintype "passive"))
      (node (ref "T2") (pin "1") (pinfunction "B_1") (pintype "passive"))
    )
    (net (code "89") (name "Net-(T2-C)") (class "Default")
      (node (ref "R47") (pin "1") (pinfunction "1_1") (pintype "passive"))
      (node (ref "R48") (pin "1") (pinfunction "1_1") (pintype "passive"))
      (node (ref "T2") (pin "3") (pinfunction "C_3") (pintype "passive"))
    )
    (net (code "90") (name "Net-(T3-B)") (class "Default")
      (node (ref "R47") (pin "2") (pinfunction "2_2") (pintype "passive"))
      (node (ref "T3") (pin "1") (pinfunction "B_1") (pintype "passive"))
    )
    (net (code "91") (name "Net-(T3-C)") (class "Default")
      (node (ref "R49") (pin "1") (pinfunction "1_1") (pintype "passive"))
      (node (ref "T3") (pin "3") (pinfunction "C_3") (pintype "passive"))
    )
    (net (code "92") (name "Net-(U$8-C1N)") (class "Default")
      (node (ref "C41") (pin "2") (pinfunction "2_2") (pintype "passive"))
      (node (ref "U$8") (pin "5") (pinfunction "C1N_5") (pintype "bidirectional"))
    )
    (net (code "93") (name "Net-(U$8-C1P)") (class "Default")
      (node (ref "C41") (pin "1") (pinfunction "1_1") (pintype "passive"))
      (node (ref "U$8") (pin "4") (pinfunction "C1P_4") (pintype "bidirectional"))
    )
    (net (code "94") (name "Net-(U$8-C2N)") (class "Default")
      (node (ref "C42") (pin "2") (pinfunction "2_2") (pintype "passive"))
      (node (ref "U$8") (pin "3") (pinfunction "C2N_3") (pintype "bidirectional"))
    )
    (net (code "95") (name "Net-(U$8-C2P)") (class "Default")
      (node (ref "C42") (pin "1") (pinfunction "1_1") (pintype "passive"))
      (node (ref "U$8") (pin "2") (pinfunction "C2P_2") (pintype "bidirectional"))
    )
    (net (code "96") (name "Net-(U$8-IREF)") (class "Default")
      (node (ref "R1") (pin "2") (pinfunction "2_2") (pintype "passive"))
      (node (ref "U$8") (pin "26") (pinfunction "IREF_26") (pintype "bidirectional"))
    )
    (net (code "97") (name "Net-(U$8-VCC)") (class "Default")
      (node (ref "C7") (pin "1") (pinfunction "1_1") (pintype "passive"))
      (node (ref "U$8") (pin "28") (pinfunction "VCC_28") (pintype "bidirectional"))
    )
    (net (code "98") (name "Net-(U$8-VCOMH)") (class "Default")
      (node (ref "C40") (pin "1") (pinfunction "1_1") (pintype "passive"))
      (node (ref "U$8") (pin "27") (pinfunction "VCOMH_27") (pintype "bidirectional"))
    )
    (net (code "99") (name "OUT2") (class "Default")
      (node (ref "CBST2") (pin "2") (pinfunction "2_2") (pintype "passive"))
      (node (ref "L5") (pin "2") (pinfunction "2_2") (pintype "bidirectional"))
      (node (ref "PS2") (pin "10") (pinfunction "SW2_2_10") (pintype "output"))
      (node (ref "PS2") (pin "11") (pinfunction "SW2_3_11") (pintype "output"))
      (node (ref "PS2") (pin "9") (pinfunction "SW2_1_9") (pintype "output"))
    )
    (net (code "100") (name "OUT3") (class "Default")
      (node (ref "CBST3") (pin "1") (pinfunction "1_1") (pintype "passive"))
      (node (ref "L8") (pin "1") (pinfunction "1_1") (pintype "bidirectional"))
      (node (ref "PS2") (pin "29") (pinfunction "SW3_29") (pintype "output"))
    )
    (net (code "101") (name "OUT4") (class "Default")
      (node (ref "CBST4") (pin "1") (pinfunction "1_1") (pintype "passive"))
      (node (ref "L6") (pin "1") (pinfunction "1_1") (pintype "bidirectional"))
      (node (ref "PS2") (pin "32") (pinfunction "SW4_32") (pintype "output"))
    )
    (net (code "102") (name "PGOOD") (class "Default")
      (node (ref "PS2") (pin "17") (pinfunction "PGOOD_17") (pintype "output"))
      (node (ref "RPMU12") (pin "1") (pinfunction "1_1") (pintype "passive"))
    )
    (net (code "103") (name "RF_EMITTER") (class "Default")
      (node (ref "R6") (pin "2") (pinfunction "2_2") (pintype "passive"))
      (node (ref "T8") (pin "G") (pinfunction "G_G") (pintype "passive"))
      (node (ref "U1") (pin "28") (pinfunction "IO17_28") (pintype "bidirectional"))
    )
    (net (code "104") (name "RF_RECEIVER") (class "Default")
      (node (ref "Q7") (pin "2") (pinfunction "E_2") (pintype "passive"))
      (node (ref "R20") (pin "2") (pinfunction "2_2") (pintype "passive"))
      (node (ref "U1") (pin "17") (pinfunction "SD2_17") (pintype "bidirectional"))
    )
    (net (code "105") (name "RPWMA") (class "Default")
      (node (ref "IC6") (pin "2") (pinfunction "INA_2") (pintype "bidirectional"))
      (node (ref "R29") (pin "1") (pinfunction "1_1") (pintype "passive"))
      (node (ref "U1") (pin "27") (pinfunction "IO16_27") (pintype "bidirectional"))
    )
    (net (code "106") (name "RPWMB") (class "Default")
      (node (ref "IC6") (pin "4") (pinfunction "INB_4") (pintype "bidirectional"))
      (node (ref "R30") (pin "1") (pinfunction "1_1") (pintype "passive"))
      (node (ref "U1") (pin "29") (pinfunction "IO5_29") (pintype "bidirectional"))
    )
    (net (code "107") (name "RST_N") (class "Default")
      (node (ref "PS2") (pin "39") (pinfunction "RST_N_39") (pintype "input"))
      (node (ref "RPMU9") (pin "1") (pinfunction "1_1") (pintype "passive"))
    )
    (net (code "108") (name "RXD") (class "Default")
      (node (ref "U1") (pin "34") (pinfunction "RXD0_34") (pintype "bidirectional"))
      (node (ref "UART") (pin "3") (pinfunction "3_3") (pintype "passive"))
    )
    (net (code "109") (name "R_EMITTER") (class "Default")
      (node (ref "R9") (pin "2") (pinfunction "2_2") (pintype "passive"))
      (node (ref "T7") (pin "G") (pinfunction "G_G") (pintype "passive"))
      (node (ref "U1") (pin "33") (pinfunction "IO21_33") (pintype "bidirectional"))
    )
    (net (code "110") (name "R_ENC_A") (class "Default")
      (node (ref "J5") (pin "1") (pinfunction "1_1") (pintype "bidirectional"))
      (node (ref "U1") (pin "7") (pinfunction "IO35_7") (pintype "input"))
    )
    (net (code "111") (name "R_ENC_B") (class "Default")
      (node (ref "J5") (pin "2") (pinfunction "2_2") (pintype "bidirectional"))
      (node (ref "U1") (pin "6") (pinfunction "IO34_6") (pintype "input"))
    )
    (net (code "112") (name "R_RECEIVER1") (class "Default")
      (node (ref "Q5") (pin "2") (pinfunction "E_2") (pintype "passive"))
      (node (ref "R18") (pin "2") (pinfunction "2_2") (pintype "passive"))
      (node (ref "U1") (pin "18") (pinfunction "SD3_18") (pintype "bidirectional"))
    )
    (net (code "113") (name "R_RECEIVER2") (class "Default")
      (node (ref "Q6") (pin "2") (pinfunction "E_2") (pintype "passive"))
      (node (ref "R19") (pin "2") (pinfunction "2_2") (pintype "passive"))
      (node (ref "U1") (pin "19") (pinfunction "CMD_19") (pintype "bidirectional"))
    )
    (net (code "114") (name "SCL") (class "Default")
      (node (ref "R2") (pin "1") (pinfunction "1_1") (pintype "passive"))
      (node (ref "U$8") (pin "18") (pinfunction "D0_18") (pintype "bidirectional"))
      (node (ref "U1") (pin "12") (pinfunction "IO27_12") (pintype "bidirectional"))
    )
    (net (code "115") (name "SCLK") (class "Default")
      (node (ref "IC3") (pin "23") (pinfunction "SCL/SCLK_23") (pintype "bidirectional"))
      (node (ref "U1") (pin "10") (pinfunction "IO25_10") (pintype "bidirectional"))
    )
    (net (code "116") (name "SCLPMU") (class "Default")
      (node (ref "PS2") (pin "43") (pinfunction "SCL_43") (pintype "input"))
      (node (ref "RPMU11") (pin "1") (pinfunction "1_1") (pintype "passive"))
    )
    (net (code "117") (name "SDA") (class "Default")
      (node (ref "R3") (pin "1") (pinfunction "1_1") (pintype "passive"))
      (node (ref "U$8") (pin "19") (pinfunction "D1_19") (pintype "bidirectional"))
      (node (ref "U$8") (pin "20") (pinfunction "D2_20") (pintype "bidirectional"))
      (node (ref "U1") (pin "37") (pinfunction "IO23_37") (pintype "bidirectional"))
    )
    (net (code "118") (name "SDAPMU") (class "Default")
      (node (ref "PS2") (pin "42") (pinfunction "SDA_42") (pintype "bidirectional"))
      (node (ref "RPMU10") (pin "1") (pinfunction "1_1") (pintype "passive"))
    )
    (net (code "119") (name "SDI") (class "Default")
      (node (ref "IC3") (pin "24") (pinfunction "SDA/SDI_24") (pintype "bidirectional"))
      (node (ref "U1") (pin "9") (pinfunction "IO33_9") (pintype "bidirectional"))
    )
    (net (code "120") (name "SDO") (class "Default")
      (node (ref "IC3") (pin "9") (pinfunction "SDO/AD0_9") (pintype "bidirectional"))
      (node (ref "U1") (pin "8") (pinfunction "IO32_8") (pintype "bidirectional"))
    )
    (net (code "121") (name "TDI") (class "Default")
      (node (ref "J3") (pin "2") (pinfunction "2_2") (pintype "passive"))
      (node (ref "U1") (pin "14") (pinfunction "IO12_14") (pintype "bidirectional"))
    )
    (net (code "122") (name "TXD") (class "Default")
      (node (ref "U1") (pin "35") (pinfunction "TXD0_35") (pintype "bidirectional"))
      (node (ref "UART") (pin "4") (pinfunction "4_4") (pintype "passive"))
    )
    (net (code "123") (name "VBATT") (class "Default")
      (node (ref "C45") (pin "1") (pinfunction "1_1") (pintype "passive"))
      (node (ref "C6") (pin "1") (pinfunction "1_1") (pintype "passive"))
      (node (ref "C8") (pin "2") (pinfunction "2_2") (pintype "passive"))
      (node (ref "CIN1") (pin "1") (pinfunction "1_1") (pintype "passive"))
      (node (ref "CIN2") (pin "1") (pinfunction "1_1") (pintype "passive"))
      (node (ref "D3") (pin "A") (pinfunction "A_A") (pintype "passive"))
      (node (ref "D5") (pin "A") (pinfunction "A_A") (pintype "passive"))
      (node (ref "IC1") (pin "9") (pinfunction "VBN_9") (pintype "bidirectional"))
      (node (ref "J2") (pin "P$1") (pinfunction "P$1_P$1") (pintype "bidirectional"))
      (node (ref "PLZ6V2B-G3/H") (pin "K") (pinfunction "K_K") (pintype "bidirectional"))
      (node (ref "PS2") (pin "22") (pinfunction "VIN_22") (pintype "power_in"))
      (node (ref "PS2") (pin "30") (pinfunction "PVIN3_30") (pintype "power_in"))
      (node (ref "PS2") (pin "31") (pinfunction "PVIN4_31") (pintype "power_in"))
      (node (ref "PS2") (pin "5") (pinfunction "PVIN1_5") (pintype "power_in"))
      (node (ref "PS2") (pin "6") (pinfunction "PVIN2_6") (pintype "power_in"))
      (node (ref "U$9") (pin "P$1") (pinfunction "1_P$1") (pintype "bidirectional"))
    )
    (net (code "124") (name "VBOOST") (class "Default")
      (node (ref "C33") (pin "1") (pinfunction "1_1") (pintype "passive"))
      (node (ref "C34") (pin "1") (pinfunction "1_1") (pintype "passive"))
      (node (ref "C35") (pin "1") (pinfunction "1_1") (pintype "passive"))
      (node (ref "C36") (pin "1") (pinfunction "1_1") (pintype "passive"))
      (node (ref "C37") (pin "1") (pinfunction "1_1") (pintype "passive"))
      (node (ref "C38") (pin "1") (pinfunction "1_1") (pintype "passive"))
      (node (ref "C46") (pin "1") (pinfunction "1_1") (pintype "passive"))
      (node (ref "C49") (pin "1") (pinfunction "1_1") (pintype "passive"))
      (node (ref "C50") (pin "1") (pinfunction "1_1") (pintype "passive"))
      (node (ref "IC1") (pin "14") (pinfunction "VOUT_1_14") (pintype "bidirectional"))
      (node (ref "IC1") (pin "15") (pinfunction "VOUT_2_15") (pintype "bidirectional"))
      (node (ref "IC1") (pin "16") (pinfunction "VOUT_3_16") (pintype "bidirectional"))
      (node (ref "IC6") (pin "6") (pinfunction "VDD_6") (pintype "bidirectional"))
      (node (ref "IC8") (pin "6") (pinfunction "VDD_6") (pintype "bidirectional"))
      (node (ref "IC9") (pin "5") (pinfunction "OUTB_5") (pintype "bidirectional"))
      (node (ref "Q10") (pin "7") (pinfunction "P1S/P2S_7") (pintype "bidirectional"))
      (node (ref "Q11") (pin "7") (pinfunction "P1S/P2S_7") (pintype "bidirectional"))
      (node (ref "R25") (pin "2") (pinfunction "2_2") (pintype "passive"))
    )
    (net (code "125") (name "VDDD") (class "Default")
      (node (ref "CVDD1") (pin "1") (pinfunction "1_1") (pintype "passive"))
      (node (ref "PS2") (pin "13") (pinfunction "ENSW2_13") (pintype "input"))
      (node (ref "PS2") (pin "20") (pinfunction "VDDD_20") (pintype "output"))
      (node (ref "PS2") (pin "27") (pinfunction "ENSW3_27") (pintype "input"))
      (node (ref "PS2") (pin "34") (pinfunction "ENSW4_34") (pintype "input"))
      (node (ref "PS2") (pin "48") (pinfunction "ENS1_48") (pintype "input"))
      (node (ref "RPMU10") (pin "2") (pinfunction "2_2") (pintype "passive"))
      (node (ref "RPMU11") (pin "2") (pinfunction "2_2") (pintype "passive"))
      (node (ref "RPMU12") (pin "2") (pinfunction "2_2") (pintype "passive"))
      (node (ref "RPMU8") (pin "2") (pinfunction "2_2") (pintype "passive"))
      (node (ref "RPMU9") (pin "2") (pinfunction "2_2") (pintype "passive"))
    )
    (net (code "126") (name "unconnected-(IC1-EN-Pad2)") (class "Default")
      (node (ref "IC1") (pin "2") (pinfunction "EN_2") (pintype "bidirectional"))
    )
    (net (code "127") (name "unconnected-(IC1-MODE-Pad13)") (class "Default")
      (node (ref "IC1") (pin "13") (pinfunction "MODE_13") (pintype "bidirectional"))
    )
    (net (code "128") (name "unconnected-(IC3-AUX-Pad7)") (class "Default")
      (node (ref "IC3") (pin "7") (pinfunction "AUX_7") (pintype "bidirectional"))
    )
    (net (code "129") (name "unconnected-(IC3-AUX_DA-Pad21)") (class "Default")
      (node (ref "IC3") (pin "21") (pinfunction "AUX_DA_21") (pintype "bidirectional"))
    )
    (net (code "130") (name "unconnected-(IC3-NC_1-Pad1)") (class "Default")
      (node (ref "IC3") (pin "1") (pinfunction "NC_1_1") (pintype "bidirectional"))
    )
    (net (code "131") (name "unconnected-(IC3-NC_2-Pad2)") (class "Default")
      (node (ref "IC3") (pin "2") (pinfunction "NC_2_2") (pintype "bidirectional"))
    )
    (net (code "132") (name "unconnected-(IC3-NC_3-Pad3)") (class "Default")
      (node (ref "IC3") (pin "3") (pinfunction "NC_3_3") (pintype "bidirectional"))
    )
    (net (code "133") (name "unconnected-(IC3-NC_4-Pad4)") (class "Default")
      (node (ref "IC3") (pin "4") (pinfunction "NC_4_4") (pintype "bidirectional"))
    )
    (net (code "134") (name "unconnected-(IC3-NC_5-Pad5)") (class "Default")
      (node (ref "IC3") (pin "5") (pinfunction "NC_5_5") (pintype "bidirectional"))
    )
    (net (code "135") (name "unconnected-(IC3-NC_6-Pad6)") (class "Default")
      (node (ref "IC3") (pin "6") (pinfunction "NC_6_6") (pintype "bidirectional"))
    )
    (net (code "136") (name "unconnected-(IC3-NC_7-Pad14)") (class "Default")
      (node (ref "IC3") (pin "14") (pinfunction "NC_7_14") (pintype "bidirectional"))
    )
    (net (code "137") (name "unconnected-(IC3-NC_8-Pad15)") (class "Default")
      (node (ref "IC3") (pin "15") (pinfunction "NC_8_15") (pintype "bidirectional"))
    )
    (net (code "138") (name "unconnected-(IC3-NC_9-Pad16)") (class "Default")
      (node (ref "IC3") (pin "16") (pinfunction "NC_9_16") (pintype "bidirectional"))
    )
    (net (code "139") (name "unconnected-(IC3-NC_10-Pad17)") (class "Default")
      (node (ref "IC3") (pin "17") (pinfunction "NC_10_17") (pintype "bidirectional"))
    )
    (net (code "140") (name "unconnected-(IC3-RESV_1-Pad19)") (class "Default")
      (node (ref "IC3") (pin "19") (pinfunction "RESV_1_19") (pintype "bidirectional"))
    )
    (net (code "141") (name "unconnected-(IC3-RESV_2-Pad20)") (class "Default")
      (node (ref "IC3") (pin "20") (pinfunction "RESV_2_20") (pintype "bidirectional"))
    )
    (net (code "142") (name "unconnected-(IC6-ENA-Pad1)") (class "Default")
      (node (ref "IC6") (pin "1") (pinfunction "ENA_1") (pintype "bidirectional"))
    )
    (net (code "143") (name "unconnected-(IC6-ENB-Pad8)") (class "Default")
      (node (ref "IC6") (pin "8") (pinfunction "ENB_8") (pintype "bidirectional"))
    )
    (net (code "144") (name "unconnected-(IC8-ENA-Pad1)") (class "Default")
      (node (ref "IC8") (pin "1") (pinfunction "ENA_1") (pintype "bidirectional"))
    )
    (net (code "145") (name "unconnected-(IC8-ENB-Pad8)") (class "Default")
      (node (ref "IC8") (pin "8") (pinfunction "ENB_8") (pintype "bidirectional"))
    )
    (net (code "146") (name "unconnected-(IC9-ENA-Pad1)") (class "Default")
      (node (ref "IC9") (pin "1") (pinfunction "ENA_1") (pintype "bidirectional"))
    )
    (net (code "147") (name "unconnected-(IC9-ENB-Pad8)") (class "Default")
      (node (ref "IC9") (pin "8") (pinfunction "ENB_8") (pintype "bidirectional"))
    )
    (net (code "148") (name "unconnected-(IC9-INA-Pad2)") (class "Default")
      (node (ref "IC9") (pin "2") (pinfunction "INA_2") (pintype "bidirectional"))
    )
    (net (code "149") (name "unconnected-(IC9-OUTA-Pad7)") (class "Default")
      (node (ref "IC9") (pin "7") (pinfunction "OUTA_7") (pintype "bidirectional"))
    )
    (net (code "150") (name "unconnected-(PS2-CE-Pad23)") (class "Default")
      (node (ref "PS2") (pin "23") (pinfunction "CE_23") (pintype "input"))
    )
    (net (code "151") (name "unconnected-(PS2-CLK_OUT-Pad44)") (class "Default")
      (node (ref "PS2") (pin "44") (pinfunction "CLK_OUT_44") (pintype "output"))
    )
    (net (code "152") (name "unconnected-(U$8-D{slash}C#-Pad15)") (class "Default")
      (node (ref "U$8") (pin "15") (pinfunction "D/C#_15") (pintype "bidirectional"))
    )
    (net (code "153") (name "unconnected-(U$8-NC_2-Pad7)") (class "Default")
      (node (ref "U$8") (pin "7") (pinfunction "NC_2_7") (pintype "bidirectional"))
    )
    (net (code "154") (name "unconnected-(U1-NC-Pad32)") (class "Default")
      (node (ref "U1") (pin "32") (pinfunction "NC_32") (pintype "bidirectional"))
    )
  )
)
